# MMC_DSP_interface.net
KiCad netlist of a schematic drawn in EAGLE
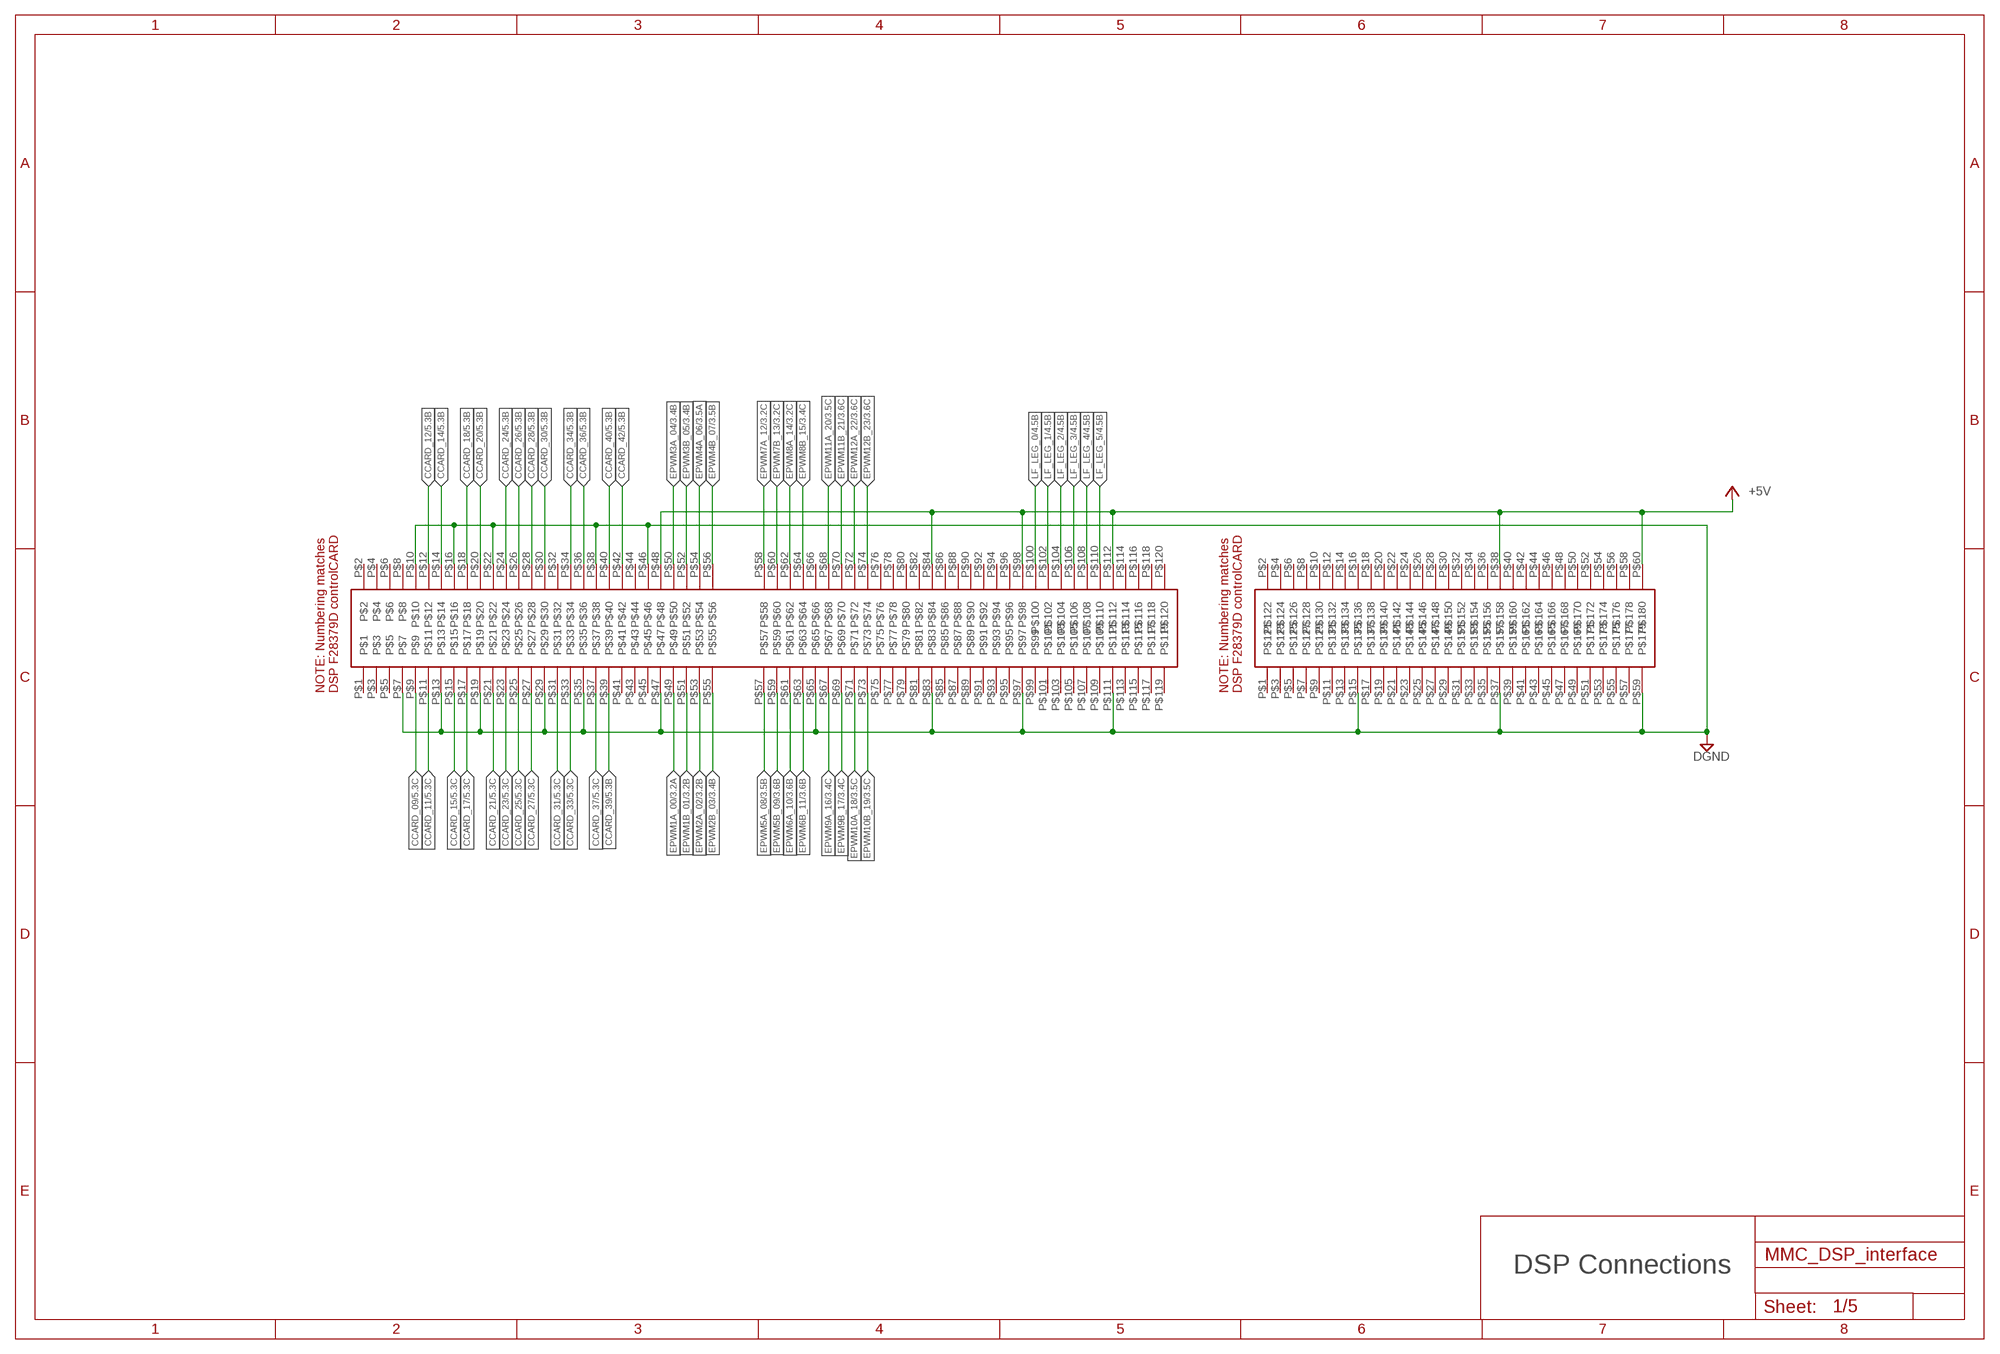
[diagram p0: schematic, sheet 1]
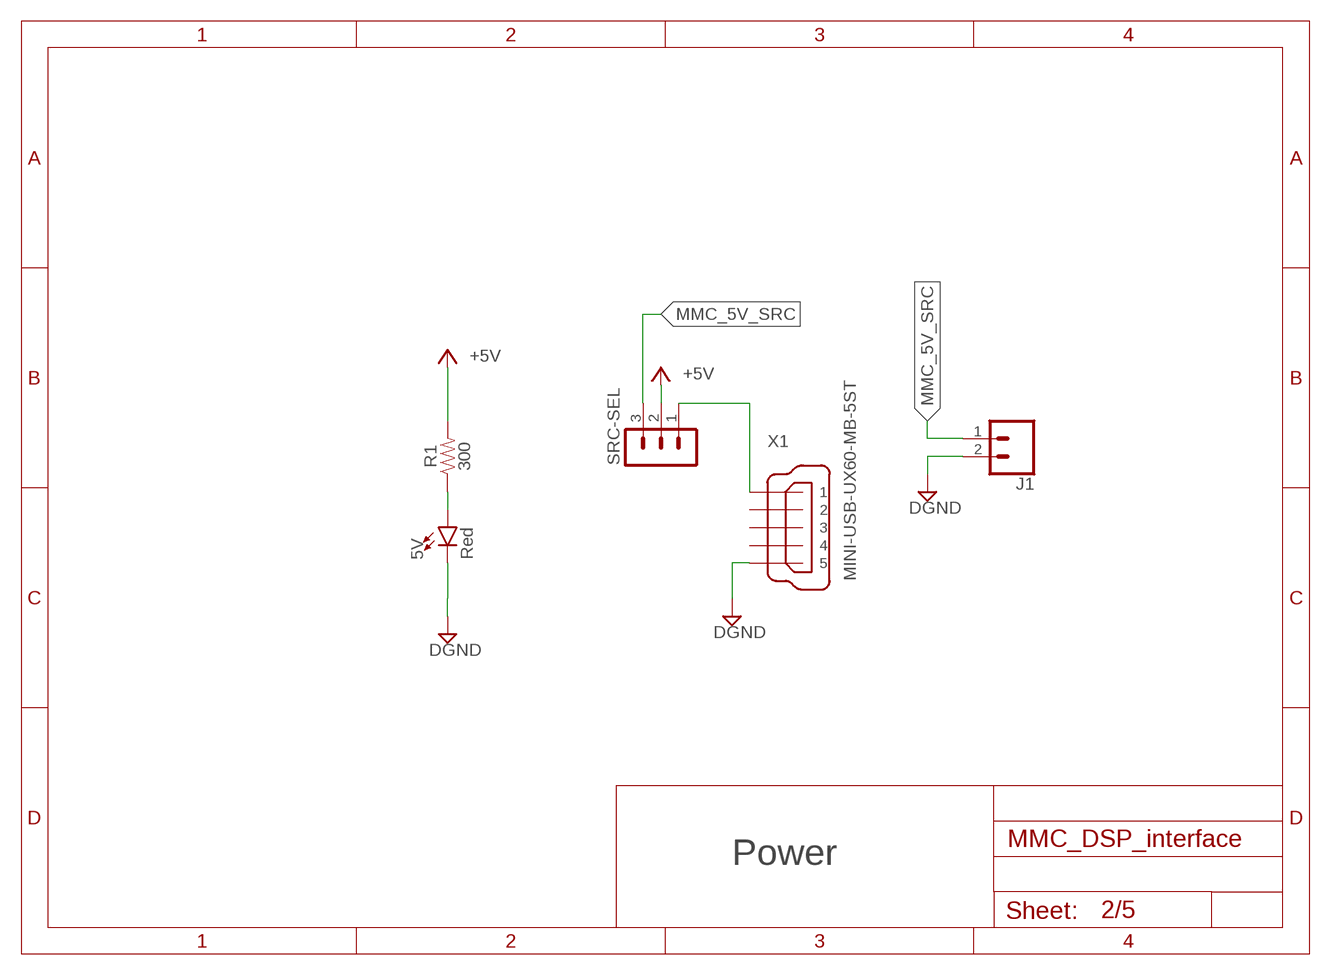
[diagram p1: schematic, sheet 2]
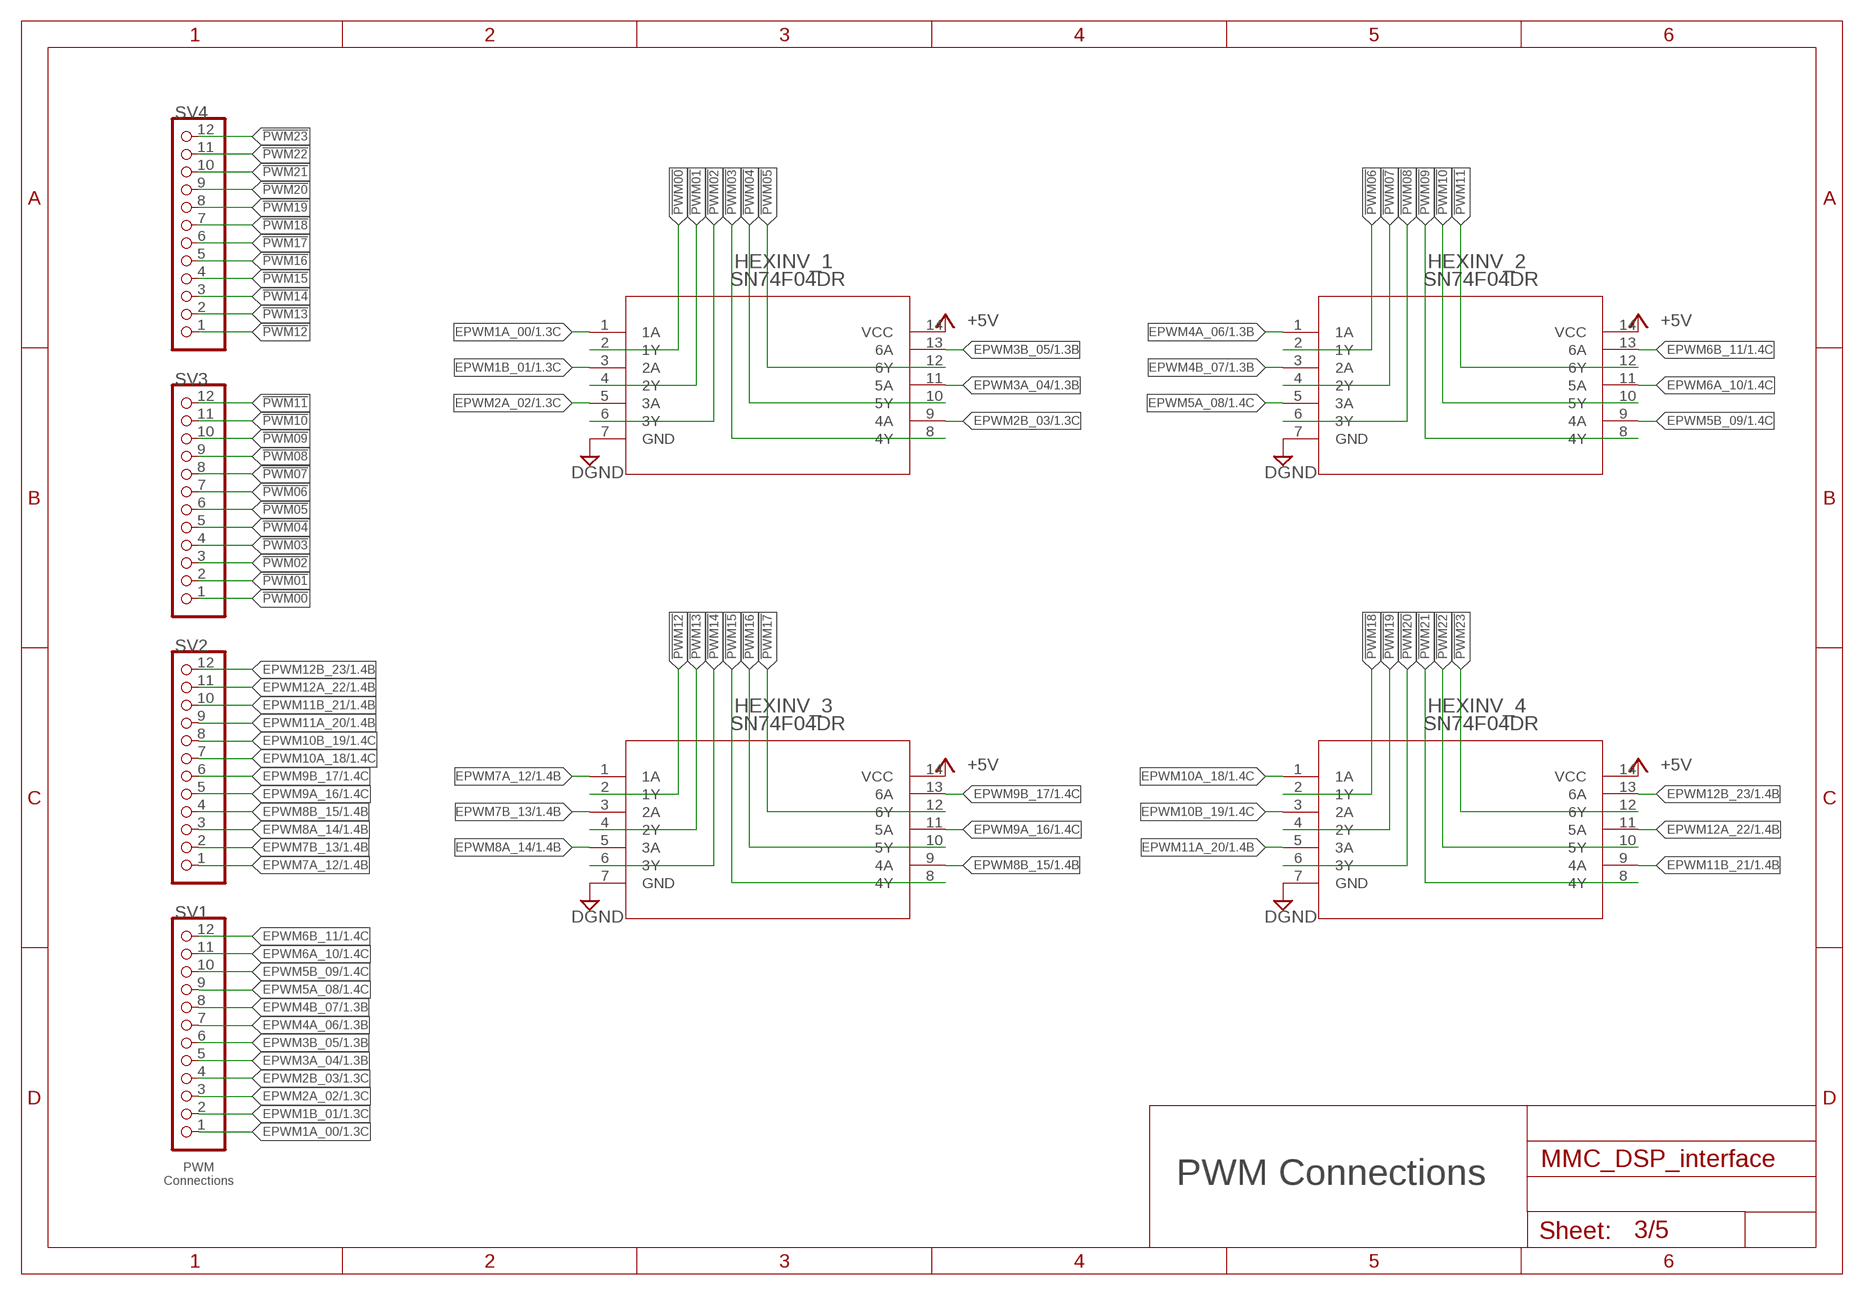
[diagram p2: schematic, sheet 3]
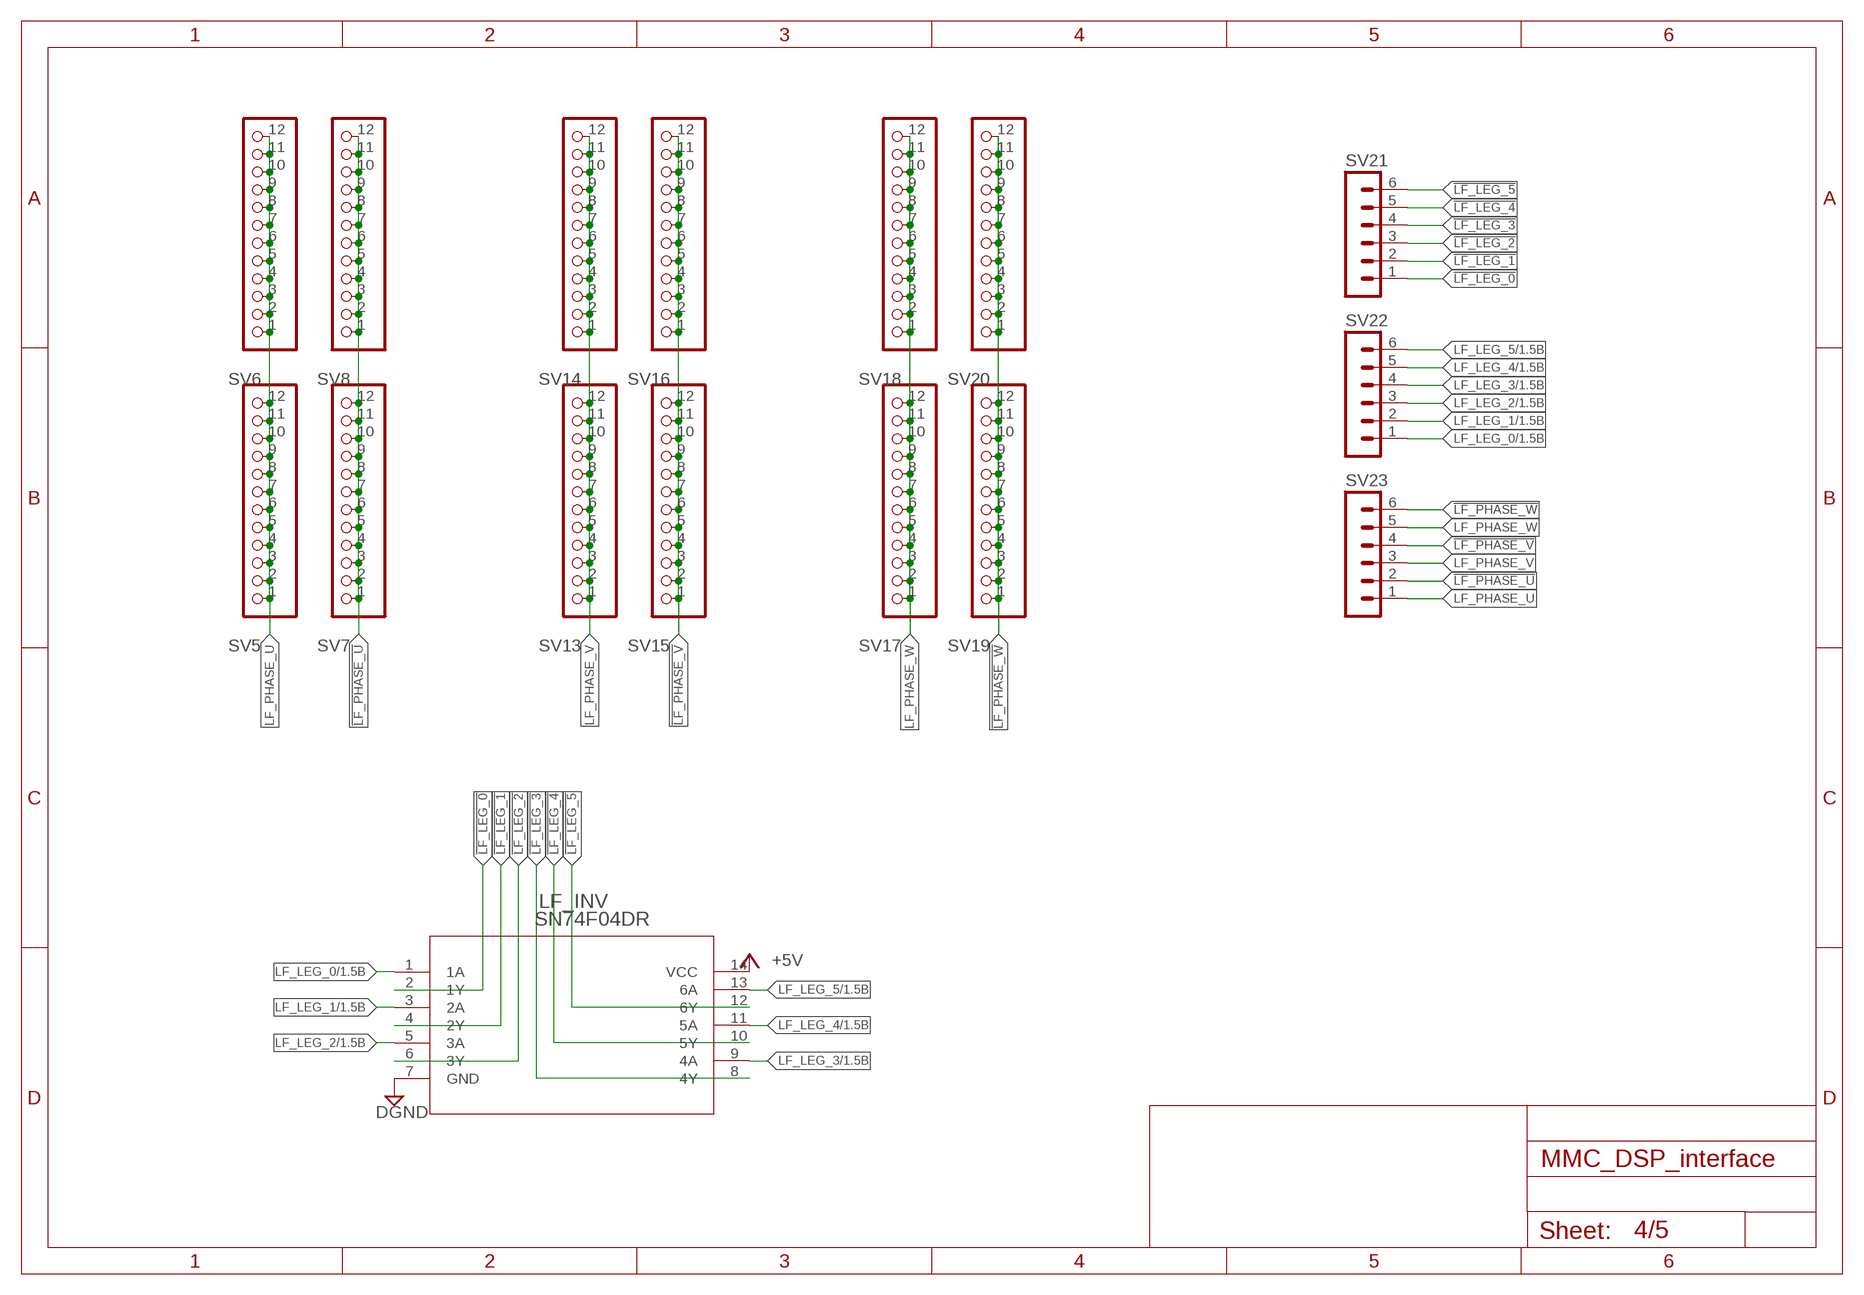
[diagram p3: schematic, sheet 4]
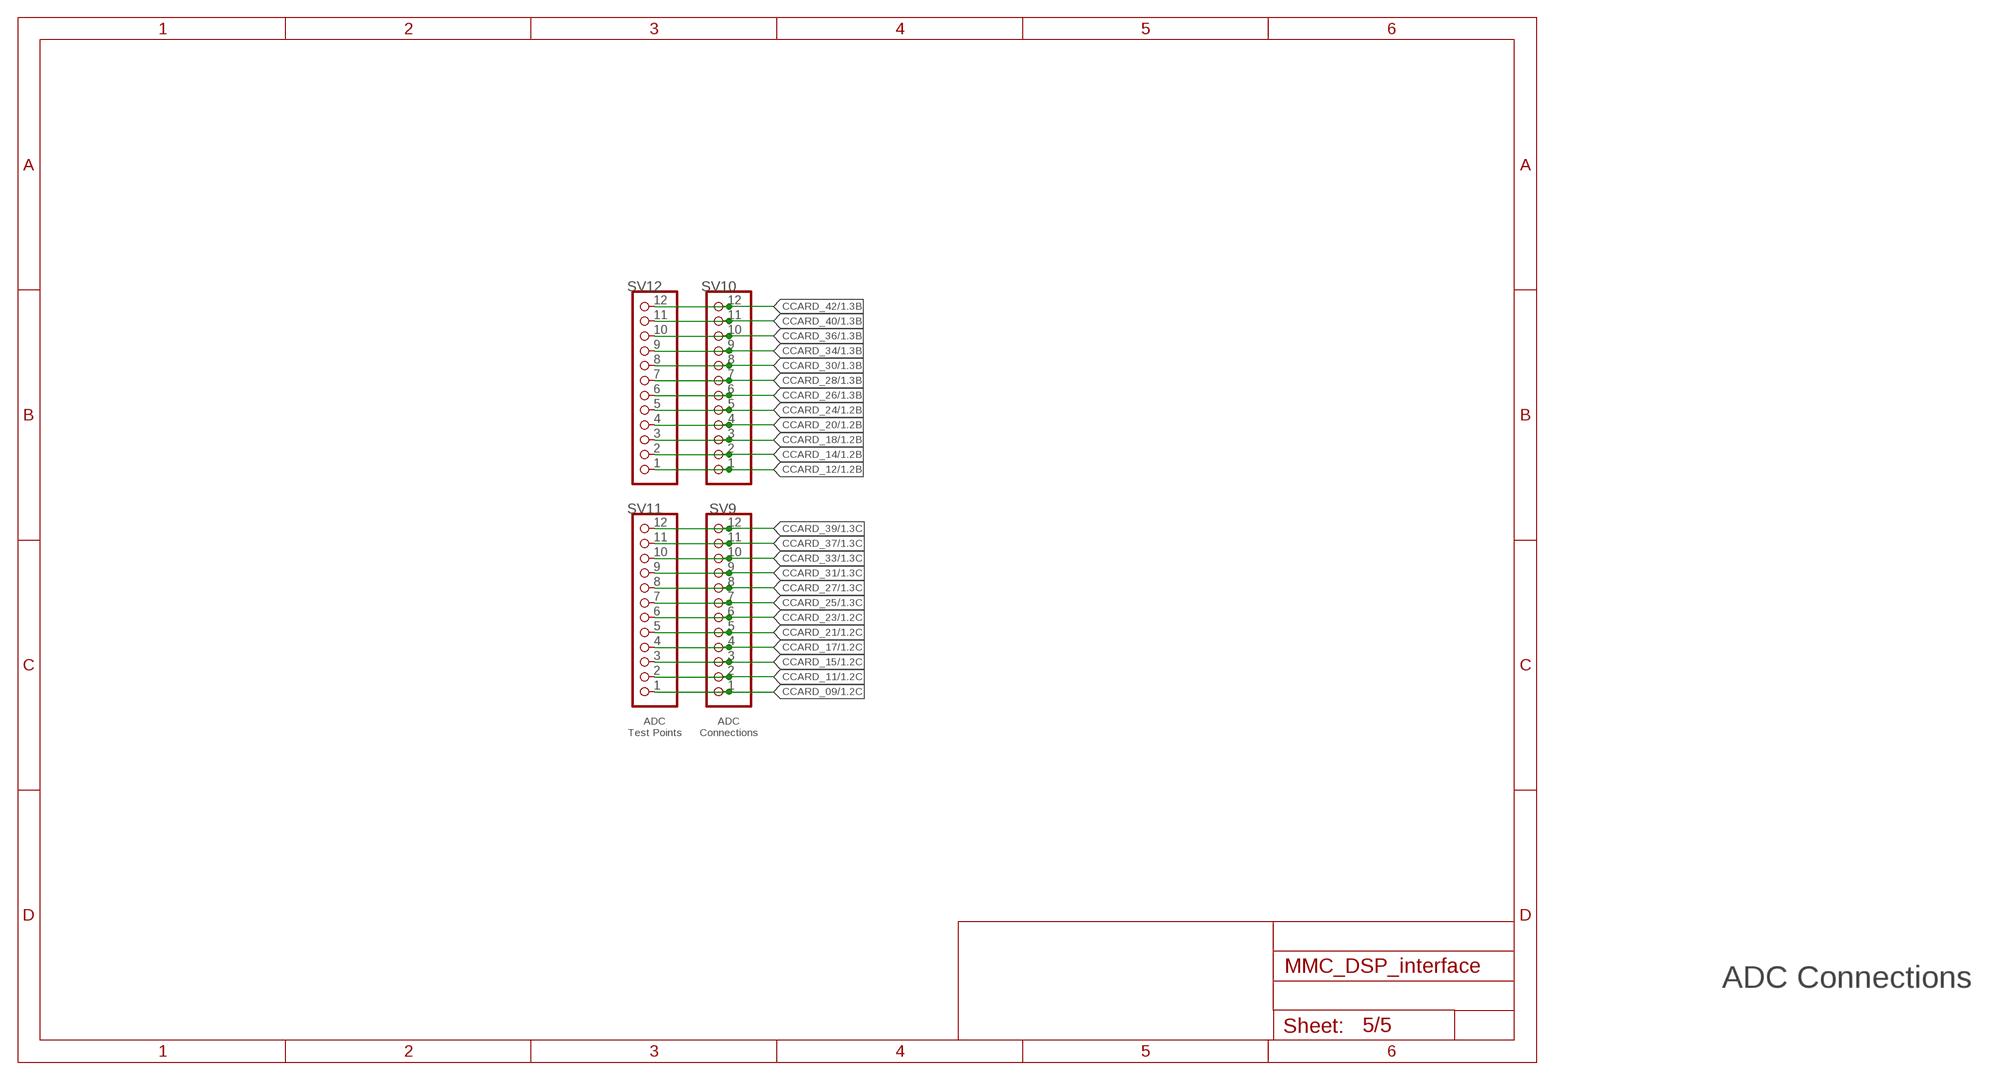
[diagram p4: schematic, sheet 5]

(export (version "E")
  (design (tool "Eeschema 10.0.6"))
  (components
    (comp (ref "5V")
      (value "Red")
      (footprint "eagle-import:LED-0603")
      (libsource (lib "eagle-import") (part "LED-RED0603-SMART"))
    )
    (comp (ref "J1")
      (value "CONN_02")
      (footprint "eagle-import:1X02")
      (libsource (lib "eagle-import") (part "CONN_02"))
    )
    (comp (ref "R1")
      (value "300")
      (footprint "eagle-import:0603")
      (libsource (lib "eagle-import") (part "300OHM-0603-1/10W-1%"))
    )
    (comp (ref "SRC-SEL")
      (value "MA03-1")
      (footprint "eagle-import:MA03-1")
      (libsource (lib "eagle-import") (part "MA03-1"))
    )
    (comp (ref "X1")
      (value "MINI-USB-UX60-MB-5ST")
      (footprint "eagle-import:UX60-MB-5ST")
      (libsource (lib "eagle-import") (part "MINI-USB-UX60-MB-5ST"))
    )
    (comp (ref "LF_INV")
      (value "SN74F04DR")
      (footprint "eagle-import:D14")
      (libsource (lib "eagle-import") (part "SN74F04DR"))
    )
    (comp (ref "SV5")
      (value "PINHD-1X12-CB")
      (footprint "eagle-import:1X12-CB")
      (libsource (lib "eagle-import") (part "PINHD-1X12-CB"))
    )
    (comp (ref "SV6")
      (value "PINHD-1X12-CB")
      (footprint "eagle-import:1X12-CB")
      (libsource (lib "eagle-import") (part "PINHD-1X12-CB"))
    )
    (comp (ref "SV7")
      (value "PINHD-1X12-CB")
      (footprint "eagle-import:1X12-CB")
      (libsource (lib "eagle-import") (part "PINHD-1X12-CB"))
    )
    (comp (ref "SV8")
      (value "PINHD-1X12-CB")
      (footprint "eagle-import:1X12-CB")
      (libsource (lib "eagle-import") (part "PINHD-1X12-CB"))
    )
    (comp (ref "SV13")
      (value "PINHD-1X12-CB")
      (footprint "eagle-import:1X12-CB")
      (libsource (lib "eagle-import") (part "PINHD-1X12-CB"))
    )
    (comp (ref "SV14")
      (value "PINHD-1X12-CB")
      (footprint "eagle-import:1X12-CB")
      (libsource (lib "eagle-import") (part "PINHD-1X12-CB"))
    )
    (comp (ref "SV15")
      (value "PINHD-1X12-CB")
      (footprint "eagle-import:1X12-CB")
      (libsource (lib "eagle-import") (part "PINHD-1X12-CB"))
    )
    (comp (ref "SV16")
      (value "PINHD-1X12-CB")
      (footprint "eagle-import:1X12-CB")
      (libsource (lib "eagle-import") (part "PINHD-1X12-CB"))
    )
    (comp (ref "SV17")
      (value "PINHD-1X12-CB")
      (footprint "eagle-import:1X12-CB")
      (libsource (lib "eagle-import") (part "PINHD-1X12-CB"))
    )
    (comp (ref "SV18")
      (value "PINHD-1X12-CB")
      (footprint "eagle-import:1X12-CB")
      (libsource (lib "eagle-import") (part "PINHD-1X12-CB"))
    )
    (comp (ref "SV19")
      (value "PINHD-1X12-CB")
      (footprint "eagle-import:1X12-CB")
      (libsource (lib "eagle-import") (part "PINHD-1X12-CB"))
    )
    (comp (ref "SV20")
      (value "PINHD-1X12-CB")
      (footprint "eagle-import:1X12-CB")
      (libsource (lib "eagle-import") (part "PINHD-1X12-CB"))
    )
    (comp (ref "SV21")
      (value "MA06-1")
      (footprint "eagle-import:MA06-1")
      (libsource (lib "eagle-import") (part "MA06-1"))
    )
    (comp (ref "SV22")
      (value "MA06-1")
      (footprint "eagle-import:MA06-1")
      (libsource (lib "eagle-import") (part "MA06-1"))
    )
    (comp (ref "SV23")
      (value "MA06-1")
      (footprint "eagle-import:MA06-1")
      (libsource (lib "eagle-import") (part "MA06-1"))
    )
    (comp (ref "HEXINV_1")
      (value "SN74F04DR")
      (footprint "eagle-import:D14")
      (libsource (lib "eagle-import") (part "SN74F04DR"))
    )
    (comp (ref "HEXINV_2")
      (value "SN74F04DR")
      (footprint "eagle-import:D14")
      (libsource (lib "eagle-import") (part "SN74F04DR"))
    )
    (comp (ref "HEXINV_3")
      (value "SN74F04DR")
      (footprint "eagle-import:D14")
      (libsource (lib "eagle-import") (part "SN74F04DR"))
    )
    (comp (ref "HEXINV_4")
      (value "SN74F04DR")
      (footprint "eagle-import:D14")
      (libsource (lib "eagle-import") (part "SN74F04DR"))
    )
    (comp (ref "SV1")
      (value "PINHD-1X12-CB")
      (footprint "eagle-import:1X12-CB")
      (libsource (lib "eagle-import") (part "PINHD-1X12-CB"))
    )
    (comp (ref "SV2")
      (value "PINHD-1X12-CB")
      (footprint "eagle-import:1X12-CB")
      (libsource (lib "eagle-import") (part "PINHD-1X12-CB"))
    )
    (comp (ref "SV3")
      (value "PINHD-1X12-CB")
      (footprint "eagle-import:1X12-CB")
      (libsource (lib "eagle-import") (part "PINHD-1X12-CB"))
    )
    (comp (ref "SV4")
      (value "PINHD-1X12-CB")
      (footprint "eagle-import:1X12-CB")
      (libsource (lib "eagle-import") (part "PINHD-1X12-CB"))
    )
    (comp (ref "U$1")
      (value "HSEC8-160-01-L-DV-A-BL")
      (footprint "eagle-import:HSEC8-160-01-L-DV-A-BL")
      (libsource (lib "eagle-import") (part "HSEC8-160-01-L-DV-A-BL"))
    )
    (comp (ref "U$2")
      (value "HSEC8-130-01-SM-DV-A")
      (footprint "eagle-import:HSEC8-130-01-SM-DV-A")
      (libsource (lib "eagle-import") (part "HSEC8-130-01-SM-DV-A"))
    )
    (comp (ref "SV9")
      (value "PINHD-1X12-CB")
      (footprint "eagle-import:1X12-CB")
      (libsource (lib "eagle-import") (part "PINHD-1X12-CB"))
    )
    (comp (ref "SV10")
      (value "PINHD-1X12-CB")
      (footprint "eagle-import:1X12-CB")
      (libsource (lib "eagle-import") (part "PINHD-1X12-CB"))
    )
    (comp (ref "SV11")
      (value "PINHD-1X12-CB")
      (footprint "eagle-import:1X12-CB")
      (libsource (lib "eagle-import") (part "PINHD-1X12-CB"))
    )
    (comp (ref "SV12")
      (value "PINHD-1X12-CB")
      (footprint "eagle-import:1X12-CB")
      (libsource (lib "eagle-import") (part "PINHD-1X12-CB"))
    )
  )
  (nets
    (net (code "1") (name "+5V") (class "Default")
      (node (ref "HEXINV_1") (pin "14") (pinfunction "VCC_14") (pintype "power_in"))
      (node (ref "HEXINV_2") (pin "14") (pinfunction "VCC_14") (pintype "power_in"))
      (node (ref "HEXINV_3") (pin "14") (pinfunction "VCC_14") (pintype "power_in"))
      (node (ref "HEXINV_4") (pin "14") (pinfunction "VCC_14") (pintype "power_in"))
      (node (ref "LF_INV") (pin "14") (pinfunction "VCC_14") (pintype "power_in"))
      (node (ref "R1") (pin "2") (pinfunction "2_2") (pintype "passive"))
      (node (ref "SRC-SEL") (pin "2") (pinfunction "2_2") (pintype "passive"))
      (node (ref "U$1") (pin "P$112") (pinfunction "P$112_P$112") (pintype "bidirectional"))
      (node (ref "U$1") (pin "P$48") (pinfunction "P$48_P$48") (pintype "bidirectional"))
      (node (ref "U$1") (pin "P$84") (pinfunction "P$84_P$84") (pintype "bidirectional"))
      (node (ref "U$1") (pin "P$98") (pinfunction "P$98_P$98") (pintype "bidirectional"))
      (node (ref "U$2") (pin "P$38") (pinfunction "P$158_P$38") (pintype "bidirectional"))
      (node (ref "U$2") (pin "P$60") (pinfunction "P$180_P$60") (pintype "bidirectional"))
    )
    (net (code "2") (name "CCARD_09") (class "Default")
      (node (ref "SV11") (pin "1") (pinfunction "1_1") (pintype "passive"))
      (node (ref "SV9") (pin "1") (pinfunction "1_1") (pintype "passive"))
      (node (ref "U$1") (pin "P$9") (pinfunction "P$9_P$9") (pintype "bidirectional"))
    )
    (net (code "3") (name "CCARD_11") (class "Default")
      (node (ref "SV11") (pin "2") (pinfunction "2_2") (pintype "passive"))
      (node (ref "SV9") (pin "2") (pinfunction "2_2") (pintype "passive"))
      (node (ref "U$1") (pin "P$11") (pinfunction "P$11_P$11") (pintype "bidirectional"))
    )
    (net (code "4") (name "CCARD_12") (class "Default")
      (node (ref "SV10") (pin "1") (pinfunction "1_1") (pintype "passive"))
      (node (ref "SV12") (pin "1") (pinfunction "1_1") (pintype "passive"))
      (node (ref "U$1") (pin "P$12") (pinfunction "P$12_P$12") (pintype "bidirectional"))
    )
    (net (code "5") (name "CCARD_14") (class "Default")
      (node (ref "SV10") (pin "2") (pinfunction "2_2") (pintype "passive"))
      (node (ref "SV12") (pin "2") (pinfunction "2_2") (pintype "passive"))
      (node (ref "U$1") (pin "P$14") (pinfunction "P$14_P$14") (pintype "bidirectional"))
    )
    (net (code "6") (name "CCARD_15") (class "Default")
      (node (ref "SV11") (pin "3") (pinfunction "3_3") (pintype "passive"))
      (node (ref "SV9") (pin "3") (pinfunction "3_3") (pintype "passive"))
      (node (ref "U$1") (pin "P$15") (pinfunction "P$15_P$15") (pintype "bidirectional"))
    )
    (net (code "7") (name "CCARD_17") (class "Default")
      (node (ref "SV11") (pin "4") (pinfunction "4_4") (pintype "passive"))
      (node (ref "SV9") (pin "4") (pinfunction "4_4") (pintype "passive"))
      (node (ref "U$1") (pin "P$17") (pinfunction "P$17_P$17") (pintype "bidirectional"))
    )
    (net (code "8") (name "CCARD_18") (class "Default")
      (node (ref "SV10") (pin "3") (pinfunction "3_3") (pintype "passive"))
      (node (ref "SV12") (pin "3") (pinfunction "3_3") (pintype "passive"))
      (node (ref "U$1") (pin "P$18") (pinfunction "P$18_P$18") (pintype "bidirectional"))
    )
    (net (code "9") (name "CCARD_20") (class "Default")
      (node (ref "SV10") (pin "4") (pinfunction "4_4") (pintype "passive"))
      (node (ref "SV12") (pin "4") (pinfunction "4_4") (pintype "passive"))
      (node (ref "U$1") (pin "P$20") (pinfunction "P$20_P$20") (pintype "bidirectional"))
    )
    (net (code "10") (name "CCARD_21") (class "Default")
      (node (ref "SV11") (pin "5") (pinfunction "5_5") (pintype "passive"))
      (node (ref "SV9") (pin "5") (pinfunction "5_5") (pintype "passive"))
      (node (ref "U$1") (pin "P$21") (pinfunction "P$21_P$21") (pintype "bidirectional"))
    )
    (net (code "11") (name "CCARD_23") (class "Default")
      (node (ref "SV11") (pin "6") (pinfunction "6_6") (pintype "passive"))
      (node (ref "SV9") (pin "6") (pinfunction "6_6") (pintype "passive"))
      (node (ref "U$1") (pin "P$23") (pinfunction "P$23_P$23") (pintype "bidirectional"))
    )
    (net (code "12") (name "CCARD_24") (class "Default")
      (node (ref "SV10") (pin "5") (pinfunction "5_5") (pintype "passive"))
      (node (ref "SV12") (pin "5") (pinfunction "5_5") (pintype "passive"))
      (node (ref "U$1") (pin "P$24") (pinfunction "P$24_P$24") (pintype "bidirectional"))
    )
    (net (code "13") (name "CCARD_25") (class "Default")
      (node (ref "SV11") (pin "7") (pinfunction "7_7") (pintype "passive"))
      (node (ref "SV9") (pin "7") (pinfunction "7_7") (pintype "passive"))
      (node (ref "U$1") (pin "P$25") (pinfunction "P$25_P$25") (pintype "bidirectional"))
    )
    (net (code "14") (name "CCARD_26") (class "Default")
      (node (ref "SV10") (pin "6") (pinfunction "6_6") (pintype "passive"))
      (node (ref "SV12") (pin "6") (pinfunction "6_6") (pintype "passive"))
      (node (ref "U$1") (pin "P$26") (pinfunction "P$26_P$26") (pintype "bidirectional"))
    )
    (net (code "15") (name "CCARD_27") (class "Default")
      (node (ref "SV11") (pin "8") (pinfunction "8_8") (pintype "passive"))
      (node (ref "SV9") (pin "8") (pinfunction "8_8") (pintype "passive"))
      (node (ref "U$1") (pin "P$27") (pinfunction "P$27_P$27") (pintype "bidirectional"))
    )
    (net (code "16") (name "CCARD_28") (class "Default")
      (node (ref "SV10") (pin "7") (pinfunction "7_7") (pintype "passive"))
      (node (ref "SV12") (pin "7") (pinfunction "7_7") (pintype "passive"))
      (node (ref "U$1") (pin "P$28") (pinfunction "P$28_P$28") (pintype "bidirectional"))
    )
    (net (code "17") (name "CCARD_30") (class "Default")
      (node (ref "SV10") (pin "8") (pinfunction "8_8") (pintype "passive"))
      (node (ref "SV12") (pin "8") (pinfunction "8_8") (pintype "passive"))
      (node (ref "U$1") (pin "P$30") (pinfunction "P$30_P$30") (pintype "bidirectional"))
    )
    (net (code "18") (name "CCARD_31") (class "Default")
      (node (ref "SV11") (pin "9") (pinfunction "9_9") (pintype "passive"))
      (node (ref "SV9") (pin "9") (pinfunction "9_9") (pintype "passive"))
      (node (ref "U$1") (pin "P$31") (pinfunction "P$31_P$31") (pintype "bidirectional"))
    )
    (net (code "19") (name "CCARD_33") (class "Default")
      (node (ref "SV11") (pin "10") (pinfunction "10_10") (pintype "passive"))
      (node (ref "SV9") (pin "10") (pinfunction "10_10") (pintype "passive"))
      (node (ref "U$1") (pin "P$33") (pinfunction "P$33_P$33") (pintype "bidirectional"))
    )
    (net (code "20") (name "CCARD_34") (class "Default")
      (node (ref "SV10") (pin "9") (pinfunction "9_9") (pintype "passive"))
      (node (ref "SV12") (pin "9") (pinfunction "9_9") (pintype "passive"))
      (node (ref "U$1") (pin "P$34") (pinfunction "P$34_P$34") (pintype "bidirectional"))
    )
    (net (code "21") (name "CCARD_36") (class "Default")
      (node (ref "SV10") (pin "10") (pinfunction "10_10") (pintype "passive"))
      (node (ref "SV12") (pin "10") (pinfunction "10_10") (pintype "passive"))
      (node (ref "U$1") (pin "P$36") (pinfunction "P$36_P$36") (pintype "bidirectional"))
    )
    (net (code "22") (name "CCARD_37") (class "Default")
      (node (ref "SV11") (pin "11") (pinfunction "11_11") (pintype "passive"))
      (node (ref "SV9") (pin "11") (pinfunction "11_11") (pintype "passive"))
      (node (ref "U$1") (pin "P$37") (pinfunction "P$37_P$37") (pintype "bidirectional"))
    )
    (net (code "23") (name "CCARD_39") (class "Default")
      (node (ref "SV11") (pin "12") (pinfunction "12_12") (pintype "passive"))
      (node (ref "SV9") (pin "12") (pinfunction "12_12") (pintype "passive"))
      (node (ref "U$1") (pin "P$39") (pinfunction "P$39_P$39") (pintype "bidirectional"))
    )
    (net (code "24") (name "CCARD_40") (class "Default")
      (node (ref "SV10") (pin "11") (pinfunction "11_11") (pintype "passive"))
      (node (ref "SV12") (pin "11") (pinfunction "11_11") (pintype "passive"))
      (node (ref "U$1") (pin "P$40") (pinfunction "P$40_P$40") (pintype "bidirectional"))
    )
    (net (code "25") (name "CCARD_42") (class "Default")
      (node (ref "SV10") (pin "12") (pinfunction "12_12") (pintype "passive"))
      (node (ref "SV12") (pin "12") (pinfunction "12_12") (pintype "passive"))
      (node (ref "U$1") (pin "P$42") (pinfunction "P$42_P$42") (pintype "bidirectional"))
    )
    (net (code "26") (name "DGND") (class "Default")
      (node (ref "5V") (pin "C") (pinfunction "C_C") (pintype "passive"))
      (node (ref "HEXINV_1") (pin "7") (pinfunction "GND_7") (pintype "power_in"))
      (node (ref "HEXINV_2") (pin "7") (pinfunction "GND_7") (pintype "power_in"))
      (node (ref "HEXINV_3") (pin "7") (pinfunction "GND_7") (pintype "power_in"))
      (node (ref "HEXINV_4") (pin "7") (pinfunction "GND_7") (pintype "power_in"))
      (node (ref "J1") (pin "2") (pinfunction "2_2") (pintype "passive"))
      (node (ref "LF_INV") (pin "7") (pinfunction "GND_7") (pintype "power_in"))
      (node (ref "U$1") (pin "P$10") (pinfunction "P$10_P$10") (pintype "bidirectional"))
      (node (ref "U$1") (pin "P$111") (pinfunction "P$111_P$111") (pintype "bidirectional"))
      (node (ref "U$1") (pin "P$13") (pinfunction "P$13_P$13") (pintype "bidirectional"))
      (node (ref "U$1") (pin "P$16") (pinfunction "P$16_P$16") (pintype "bidirectional"))
      (node (ref "U$1") (pin "P$19") (pinfunction "P$19_P$19") (pintype "bidirectional"))
      (node (ref "U$1") (pin "P$22") (pinfunction "P$22_P$22") (pintype "bidirectional"))
      (node (ref "U$1") (pin "P$29") (pinfunction "P$29_P$29") (pintype "bidirectional"))
      (node (ref "U$1") (pin "P$35") (pinfunction "P$35_P$35") (pintype "bidirectional"))
      (node (ref "U$1") (pin "P$38") (pinfunction "P$38_P$38") (pintype "bidirectional"))
      (node (ref "U$1") (pin "P$46") (pinfunction "P$46_P$46") (pintype "bidirectional"))
      (node (ref "U$1") (pin "P$47") (pinfunction "P$47_P$47") (pintype "bidirectional"))
      (node (ref "U$1") (pin "P$65") (pinfunction "P$65_P$65") (pintype "bidirectional"))
      (node (ref "U$1") (pin "P$7") (pinfunction "P$7_P$7") (pintype "bidirectional"))
      (node (ref "U$1") (pin "P$83") (pinfunction "P$83_P$83") (pintype "bidirectional"))
      (node (ref "U$1") (pin "P$97") (pinfunction "P$97_P$97") (pintype "bidirectional"))
      (node (ref "U$2") (pin "P$15") (pinfunction "P$135_P$15") (pintype "bidirectional"))
      (node (ref "U$2") (pin "P$37") (pinfunction "P$157_P$37") (pintype "bidirectional"))
      (node (ref "U$2") (pin "P$59") (pinfunction "P$179_P$59") (pintype "bidirectional"))
      (node (ref "X1") (pin "5") (pinfunction "5_5") (pintype "input"))
    )
    (net (code "27") (name "EPWM1A_00") (class "Default")
      (node (ref "HEXINV_1") (pin "1") (pinfunction "1A_1") (pintype "input"))
      (node (ref "SV1") (pin "1") (pinfunction "1_1") (pintype "passive"))
      (node (ref "U$1") (pin "P$49") (pinfunction "P$49_P$49") (pintype "bidirectional"))
    )
    (net (code "28") (name "EPWM1B_01") (class "Default")
      (node (ref "HEXINV_1") (pin "3") (pinfunction "2A_3") (pintype "input"))
      (node (ref "SV1") (pin "2") (pinfunction "2_2") (pintype "passive"))
      (node (ref "U$1") (pin "P$51") (pinfunction "P$51_P$51") (pintype "bidirectional"))
    )
    (net (code "29") (name "EPWM2A_02") (class "Default")
      (node (ref "HEXINV_1") (pin "5") (pinfunction "3A_5") (pintype "input"))
      (node (ref "SV1") (pin "3") (pinfunction "3_3") (pintype "passive"))
      (node (ref "U$1") (pin "P$53") (pinfunction "P$53_P$53") (pintype "bidirectional"))
    )
    (net (code "30") (name "EPWM2B_03") (class "Default")
      (node (ref "HEXINV_1") (pin "9") (pinfunction "4A_9") (pintype "input"))
      (node (ref "SV1") (pin "4") (pinfunction "4_4") (pintype "passive"))
      (node (ref "U$1") (pin "P$55") (pinfunction "P$55_P$55") (pintype "bidirectional"))
    )
    (net (code "31") (name "EPWM3A_04") (class "Default")
      (node (ref "HEXINV_1") (pin "11") (pinfunction "5A_11") (pintype "input"))
      (node (ref "SV1") (pin "5") (pinfunction "5_5") (pintype "passive"))
      (node (ref "U$1") (pin "P$50") (pinfunction "P$50_P$50") (pintype "bidirectional"))
    )
    (net (code "32") (name "EPWM3B_05") (class "Default")
      (node (ref "HEXINV_1") (pin "13") (pinfunction "6A_13") (pintype "input"))
      (node (ref "SV1") (pin "6") (pinfunction "6_6") (pintype "passive"))
      (node (ref "U$1") (pin "P$52") (pinfunction "P$52_P$52") (pintype "bidirectional"))
    )
    (net (code "33") (name "EPWM4A_06") (class "Default")
      (node (ref "HEXINV_2") (pin "1") (pinfunction "1A_1") (pintype "input"))
      (node (ref "SV1") (pin "7") (pinfunction "7_7") (pintype "passive"))
      (node (ref "U$1") (pin "P$54") (pinfunction "P$54_P$54") (pintype "bidirectional"))
    )
    (net (code "34") (name "EPWM4B_07") (class "Default")
      (node (ref "HEXINV_2") (pin "3") (pinfunction "2A_3") (pintype "input"))
      (node (ref "SV1") (pin "8") (pinfunction "8_8") (pintype "passive"))
      (node (ref "U$1") (pin "P$56") (pinfunction "P$56_P$56") (pintype "bidirectional"))
    )
    (net (code "35") (name "EPWM5A_08") (class "Default")
      (node (ref "HEXINV_2") (pin "5") (pinfunction "3A_5") (pintype "input"))
      (node (ref "SV1") (pin "9") (pinfunction "9_9") (pintype "passive"))
      (node (ref "U$1") (pin "P$57") (pinfunction "P$57_P$57") (pintype "bidirectional"))
    )
    (net (code "36") (name "EPWM5B_09") (class "Default")
      (node (ref "HEXINV_2") (pin "9") (pinfunction "4A_9") (pintype "input"))
      (node (ref "SV1") (pin "10") (pinfunction "10_10") (pintype "passive"))
      (node (ref "U$1") (pin "P$59") (pinfunction "P$59_P$59") (pintype "bidirectional"))
    )
    (net (code "37") (name "EPWM6A_10") (class "Default")
      (node (ref "HEXINV_2") (pin "11") (pinfunction "5A_11") (pintype "input"))
      (node (ref "SV1") (pin "11") (pinfunction "11_11") (pintype "passive"))
      (node (ref "U$1") (pin "P$61") (pinfunction "P$61_P$61") (pintype "bidirectional"))
    )
    (net (code "38") (name "EPWM6B_11") (class "Default")
      (node (ref "HEXINV_2") (pin "13") (pinfunction "6A_13") (pintype "input"))
      (node (ref "SV1") (pin "12") (pinfunction "12_12") (pintype "passive"))
      (node (ref "U$1") (pin "P$63") (pinfunction "P$63_P$63") (pintype "bidirectional"))
    )
    (net (code "39") (name "EPWM7A_12") (class "Default")
      (node (ref "HEXINV_3") (pin "1") (pinfunction "1A_1") (pintype "input"))
      (node (ref "SV2") (pin "1") (pinfunction "1_1") (pintype "passive"))
      (node (ref "U$1") (pin "P$58") (pinfunction "P$58_P$58") (pintype "bidirectional"))
    )
    (net (code "40") (name "EPWM7B_13") (class "Default")
      (node (ref "HEXINV_3") (pin "3") (pinfunction "2A_3") (pintype "input"))
      (node (ref "SV2") (pin "2") (pinfunction "2_2") (pintype "passive"))
      (node (ref "U$1") (pin "P$60") (pinfunction "P$60_P$60") (pintype "bidirectional"))
    )
    (net (code "41") (name "EPWM8A_14") (class "Default")
      (node (ref "HEXINV_3") (pin "5") (pinfunction "3A_5") (pintype "input"))
      (node (ref "SV2") (pin "3") (pinfunction "3_3") (pintype "passive"))
      (node (ref "U$1") (pin "P$62") (pinfunction "P$62_P$62") (pintype "bidirectional"))
    )
    (net (code "42") (name "EPWM8B_15") (class "Default")
      (node (ref "HEXINV_3") (pin "9") (pinfunction "4A_9") (pintype "input"))
      (node (ref "SV2") (pin "4") (pinfunction "4_4") (pintype "passive"))
      (node (ref "U$1") (pin "P$64") (pinfunction "P$64_P$64") (pintype "bidirectional"))
    )
    (net (code "43") (name "EPWM9A_16") (class "Default")
      (node (ref "HEXINV_3") (pin "11") (pinfunction "5A_11") (pintype "input"))
      (node (ref "SV2") (pin "5") (pinfunction "5_5") (pintype "passive"))
      (node (ref "U$1") (pin "P$67") (pinfunction "P$67_P$67") (pintype "bidirectional"))
    )
    (net (code "44") (name "EPWM9B_17") (class "Default")
      (node (ref "HEXINV_3") (pin "13") (pinfunction "6A_13") (pintype "input"))
      (node (ref "SV2") (pin "6") (pinfunction "6_6") (pintype "passive"))
      (node (ref "U$1") (pin "P$69") (pinfunction "P$69_P$69") (pintype "bidirectional"))
    )
    (net (code "45") (name "EPWM10A_18") (class "Default")
      (node (ref "HEXINV_4") (pin "1") (pinfunction "1A_1") (pintype "input"))
      (node (ref "SV2") (pin "7") (pinfunction "7_7") (pintype "passive"))
      (node (ref "U$1") (pin "P$71") (pinfunction "P$71_P$71") (pintype "bidirectional"))
    )
    (net (code "46") (name "EPWM10B_19") (class "Default")
      (node (ref "HEXINV_4") (pin "3") (pinfunction "2A_3") (pintype "input"))
      (node (ref "SV2") (pin "8") (pinfunction "8_8") (pintype "passive"))
      (node (ref "U$1") (pin "P$73") (pinfunction "P$73_P$73") (pintype "bidirectional"))
    )
    (net (code "47") (name "EPWM11A_20") (class "Default")
      (node (ref "HEXINV_4") (pin "5") (pinfunction "3A_5") (pintype "input"))
      (node (ref "SV2") (pin "9") (pinfunction "9_9") (pintype "passive"))
      (node (ref "U$1") (pin "P$68") (pinfunction "P$68_P$68") (pintype "bidirectional"))
    )
    (net (code "48") (name "EPWM11B_21") (class "Default")
      (node (ref "HEXINV_4") (pin "9") (pinfunction "4A_9") (pintype "input"))
      (node (ref "SV2") (pin "10") (pinfunction "10_10") (pintype "passive"))
      (node (ref "U$1") (pin "P$70") (pinfunction "P$70_P$70") (pintype "bidirectional"))
    )
    (net (code "49") (name "EPWM12A_22") (class "Default")
      (node (ref "HEXINV_4") (pin "11") (pinfunction "5A_11") (pintype "input"))
      (node (ref "SV2") (pin "11") (pinfunction "11_11") (pintype "passive"))
      (node (ref "U$1") (pin "P$72") (pinfunction "P$72_P$72") (pintype "bidirectional"))
    )
    (net (code "50") (name "EPWM12B_23") (class "Default")
      (node (ref "HEXINV_4") (pin "13") (pinfunction "6A_13") (pintype "input"))
      (node (ref "SV2") (pin "12") (pinfunction "12_12") (pintype "passive"))
      (node (ref "U$1") (pin "P$74") (pinfunction "P$74_P$74") (pintype "bidirectional"))
    )
    (net (code "51") (name "LF_LEG_0") (class "Default")
      (node (ref "LF_INV") (pin "1") (pinfunction "1A_1") (pintype "input"))
      (node (ref "SV22") (pin "1") (pinfunction "1_1") (pintype "passive"))
      (node (ref "U$1") (pin "P$100") (pinfunction "P$100_P$100") (pintype "bidirectional"))
    )
    (net (code "52") (name "LF_LEG_1") (class "Default")
      (node (ref "LF_INV") (pin "3") (pinfunction "2A_3") (pintype "input"))
      (node (ref "SV22") (pin "2") (pinfunction "2_2") (pintype "passive"))
      (node (ref "U$1") (pin "P$102") (pinfunction "P$102_P$102") (pintype "bidirectional"))
    )
    (net (code "53") (name "LF_LEG_2") (class "Default")
      (node (ref "LF_INV") (pin "5") (pinfunction "3A_5") (pintype "input"))
      (node (ref "SV22") (pin "3") (pinfunction "3_3") (pintype "passive"))
      (node (ref "U$1") (pin "P$104") (pinfunction "P$104_P$104") (pintype "bidirectional"))
    )
    (net (code "54") (name "LF_LEG_3") (class "Default")
      (node (ref "LF_INV") (pin "9") (pinfunction "4A_9") (pintype "input"))
      (node (ref "SV22") (pin "4") (pinfunction "4_4") (pintype "passive"))
      (node (ref "U$1") (pin "P$106") (pinfunction "P$106_P$106") (pintype "bidirectional"))
    )
    (net (code "55") (name "LF_LEG_4") (class "Default")
      (node (ref "LF_INV") (pin "11") (pinfunction "5A_11") (pintype "input"))
      (node (ref "SV22") (pin "5") (pinfunction "5_5") (pintype "passive"))
      (node (ref "U$1") (pin "P$108") (pinfunction "P$108_P$108") (pintype "bidirectional"))
    )
    (net (code "56") (name "LF_LEG_5") (class "Default")
      (node (ref "LF_INV") (pin "13") (pinfunction "6A_13") (pintype "input"))
      (node (ref "SV22") (pin "6") (pinfunction "6_6") (pintype "passive"))
      (node (ref "U$1") (pin "P$110") (pinfunction "P$110_P$110") (pintype "bidirectional"))
    )
    (net (code "57") (name "LF_PHASE_U") (class "Default")
      (node (ref "SV23") (pin "1") (pinfunction "1_1") (pintype "passive"))
      (node (ref "SV5") (pin "1") (pinfunction "1_1") (pintype "passive"))
      (node (ref "SV5") (pin "10") (pinfunction "10_10") (pintype "passive"))
      (node (ref "SV5") (pin "11") (pinfunction "11_11") (pintype "passive"))
      (node (ref "SV5") (pin "12") (pinfunction "12_12") (pintype "passive"))
      (node (ref "SV5") (pin "2") (pinfunction "2_2") (pintype "passive"))
      (node (ref "SV5") (pin "3") (pinfunction "3_3") (pintype "passive"))
      (node (ref "SV5") (pin "4") (pinfunction "4_4") (pintype "passive"))
      (node (ref "SV5") (pin "5") (pinfunction "5_5") (pintype "passive"))
      (node (ref "SV5") (pin "6") (pinfunction "6_6") (pintype "passive"))
      (node (ref "SV5") (pin "7") (pinfunction "7_7") (pintype "passive"))
      (node (ref "SV5") (pin "8") (pinfunction "8_8") (pintype "passive"))
      (node (ref "SV5") (pin "9") (pinfunction "9_9") (pintype "passive"))
      (node (ref "SV6") (pin "1") (pinfunction "1_1") (pintype "passive"))
      (node (ref "SV6") (pin "10") (pinfunction "10_10") (pintype "passive"))
      (node (ref "SV6") (pin "11") (pinfunction "11_11") (pintype "passive"))
      (node (ref "SV6") (pin "12") (pinfunction "12_12") (pintype "passive"))
      (node (ref "SV6") (pin "2") (pinfunction "2_2") (pintype "passive"))
      (node (ref "SV6") (pin "3") (pinfunction "3_3") (pintype "passive"))
      (node (ref "SV6") (pin "4") (pinfunction "4_4") (pintype "passive"))
      (node (ref "SV6") (pin "5") (pinfunction "5_5") (pintype "passive"))
      (node (ref "SV6") (pin "6") (pinfunction "6_6") (pintype "passive"))
      (node (ref "SV6") (pin "7") (pinfunction "7_7") (pintype "passive"))
      (node (ref "SV6") (pin "8") (pinfunction "8_8") (pintype "passive"))
      (node (ref "SV6") (pin "9") (pinfunction "9_9") (pintype "passive"))
    )
    (net (code "58") (name "LF_PHASE_V") (class "Default")
      (node (ref "SV13") (pin "1") (pinfunction "1_1") (pintype "passive"))
      (node (ref "SV13") (pin "10") (pinfunction "10_10") (pintype "passive"))
      (node (ref "SV13") (pin "11") (pinfunction "11_11") (pintype "passive"))
      (node (ref "SV13") (pin "12") (pinfunction "12_12") (pintype "passive"))
      (node (ref "SV13") (pin "2") (pinfunction "2_2") (pintype "passive"))
      (node (ref "SV13") (pin "3") (pinfunction "3_3") (pintype "passive"))
      (node (ref "SV13") (pin "4") (pinfunction "4_4") (pintype "passive"))
      (node (ref "SV13") (pin "5") (pinfunction "5_5") (pintype "passive"))
      (node (ref "SV13") (pin "6") (pinfunction "6_6") (pintype "passive"))
      (node (ref "SV13") (pin "7") (pinfunction "7_7") (pintype "passive"))
      (node (ref "SV13") (pin "8") (pinfunction "8_8") (pintype "passive"))
      (node (ref "SV13") (pin "9") (pinfunction "9_9") (pintype "passive"))
      (node (ref "SV14") (pin "1") (pinfunction "1_1") (pintype "passive"))
      (node (ref "SV14") (pin "10") (pinfunction "10_10") (pintype "passive"))
      (node (ref "SV14") (pin "11") (pinfunction "11_11") (pintype "passive"))
      (node (ref "SV14") (pin "12") (pinfunction "12_12") (pintype "passive"))
      (node (ref "SV14") (pin "2") (pinfunction "2_2") (pintype "passive"))
      (node (ref "SV14") (pin "3") (pinfunction "3_3") (pintype "passive"))
      (node (ref "SV14") (pin "4") (pinfunction "4_4") (pintype "passive"))
      (node (ref "SV14") (pin "5") (pinfunction "5_5") (pintype "passive"))
      (node (ref "SV14") (pin "6") (pinfunction "6_6") (pintype "passive"))
      (node (ref "SV14") (pin "7") (pinfunction "7_7") (pintype "passive"))
      (node (ref "SV14") (pin "8") (pinfunction "8_8") (pintype "passive"))
      (node (ref "SV14") (pin "9") (pinfunction "9_9") (pintype "passive"))
      (node (ref "SV23") (pin "3") (pinfunction "3_3") (pintype "passive"))
    )
    (net (code "59") (name "LF_PHASE_W") (class "Default")
      (node (ref "SV17") (pin "1") (pinfunction "1_1") (pintype "passive"))
      (node (ref "SV17") (pin "10") (pinfunction "10_10") (pintype "passive"))
      (node (ref "SV17") (pin "11") (pinfunction "11_11") (pintype "passive"))
      (node (ref "SV17") (pin "12") (pinfunction "12_12") (pintype "passive"))
      (node (ref "SV17") (pin "2") (pinfunction "2_2") (pintype "passive"))
      (node (ref "SV17") (pin "3") (pinfunction "3_3") (pintype "passive"))
      (node (ref "SV17") (pin "4") (pinfunction "4_4") (pintype "passive"))
      (node (ref "SV17") (pin "5") (pinfunction "5_5") (pintype "passive"))
      (node (ref "SV17") (pin "6") (pinfunction "6_6") (pintype "passive"))
      (node (ref "SV17") (pin "7") (pinfunction "7_7") (pintype "passive"))
      (node (ref "SV17") (pin "8") (pinfunction "8_8") (pintype "passive"))
      (node (ref "SV17") (pin "9") (pinfunction "9_9") (pintype "passive"))
      (node (ref "SV18") (pin "1") (pinfunction "1_1") (pintype "passive"))
      (node (ref "SV18") (pin "10") (pinfunction "10_10") (pintype "passive"))
      (node (ref "SV18") (pin "11") (pinfunction "11_11") (pintype "passive"))
      (node (ref "SV18") (pin "12") (pinfunction "12_12") (pintype "passive"))
      (node (ref "SV18") (pin "2") (pinfunction "2_2") (pintype "passive"))
      (node (ref "SV18") (pin "3") (pinfunction "3_3") (pintype "passive"))
      (node (ref "SV18") (pin "4") (pinfunction "4_4") (pintype "passive"))
      (node (ref "SV18") (pin "5") (pinfunction "5_5") (pintype "passive"))
      (node (ref "SV18") (pin "6") (pinfunction "6_6") (pintype "passive"))
      (node (ref "SV18") (pin "7") (pinfunction "7_7") (pintype "passive"))
      (node (ref "SV18") (pin "8") (pinfunction "8_8") (pintype "passive"))
      (node (ref "SV18") (pin "9") (pinfunction "9_9") (pintype "passive"))
      (node (ref "SV23") (pin "5") (pinfunction "5_5") (pintype "passive"))
    )
    (net (code "60") (name "MMC_5V_SRC") (class "Default")
      (node (ref "J1") (pin "1") (pinfunction "1_1") (pintype "passive"))
      (node (ref "SRC-SEL") (pin "3") (pinfunction "3_3") (pintype "passive"))
    )
    (net (code "61") (name "Net-(5V-PadA)") (class "Default")
      (node (ref "5V") (pin "A") (pinfunction "A_A") (pintype "passive"))
      (node (ref "R1") (pin "1") (pinfunction "1_1") (pintype "passive"))
    )
    (net (code "62") (name "Net-(SRC-SEL-Pad1)") (class "Default")
      (node (ref "SRC-SEL") (pin "1") (pinfunction "1_1") (pintype "passive"))
      (node (ref "X1") (pin "1") (pinfunction "1_1") (pintype "input"))
    )
    (net (code "63") (name "unconnected-(U$1-PadP$1)") (class "Default")
      (node (ref "U$1") (pin "P$1") (pinfunction "P$1_P$1") (pintype "bidirectional"))
    )
    (net (code "64") (name "unconnected-(U$1-PadP$2)") (class "Default")
      (node (ref "U$1") (pin "P$2") (pinfunction "P$2_P$2") (pintype "bidirectional"))
    )
    (net (code "65") (name "unconnected-(U$1-PadP$3)") (class "Default")
      (node (ref "U$1") (pin "P$3") (pinfunction "P$3_P$3") (pintype "bidirectional"))
    )
    (net (code "66") (name "unconnected-(U$1-PadP$4)") (class "Default")
      (node (ref "U$1") (pin "P$4") (pinfunction "P$4_P$4") (pintype "bidirectional"))
    )
    (net (code "67") (name "unconnected-(U$1-PadP$5)") (class "Default")
      (node (ref "U$1") (pin "P$5") (pinfunction "P$5_P$5") (pintype "bidirectional"))
    )
    (net (code "68") (name "unconnected-(U$1-PadP$6)") (class "Default")
      (node (ref "U$1") (pin "P$6") (pinfunction "P$6_P$6") (pintype "bidirectional"))
    )
    (net (code "69") (name "unconnected-(U$1-PadP$8)") (class "Default")
      (node (ref "U$1") (pin "P$8") (pinfunction "P$8_P$8") (pintype "bidirectional"))
    )
    (net (code "70") (name "unconnected-(U$1-PadP$32)") (class "Default")
      (node (ref "U$1") (pin "P$32") (pinfunction "P$32_P$32") (pintype "bidirectional"))
    )
    (net (code "71") (name "unconnected-(U$1-PadP$41)") (class "Default")
      (node (ref "U$1") (pin "P$41") (pinfunction "P$41_P$41") (pintype "bidirectional"))
    )
    (net (code "72") (name "unconnected-(U$1-PadP$43)") (class "Default")
      (node (ref "U$1") (pin "P$43") (pinfunction "P$43_P$43") (pintype "bidirectional"))
    )
    (net (code "73") (name "unconnected-(U$1-PadP$44)") (class "Default")
      (node (ref "U$1") (pin "P$44") (pinfunction "P$44_P$44") (pintype "bidirectional"))
    )
    (net (code "74") (name "unconnected-(U$1-PadP$45)") (class "Default")
      (node (ref "U$1") (pin "P$45") (pinfunction "P$45_P$45") (pintype "bidirectional"))
    )
    (net (code "75") (name "unconnected-(U$1-PadP$66)") (class "Default")
      (node (ref "U$1") (pin "P$66") (pinfunction "P$66_P$66") (pintype "bidirectional"))
    )
    (net (code "76") (name "unconnected-(U$1-PadP$75)") (class "Default")
      (node (ref "U$1") (pin "P$75") (pinfunction "P$75_P$75") (pintype "bidirectional"))
    )
    (net (code "77") (name "unconnected-(U$1-PadP$76)") (class "Default")
      (node (ref "U$1") (pin "P$76") (pinfunction "P$76_P$76") (pintype "bidirectional"))
    )
    (net (code "78") (name "unconnected-(U$1-PadP$77)") (class "Default")
      (node (ref "U$1") (pin "P$77") (pinfunction "P$77_P$77") (pintype "bidirectional"))
    )
    (net (code "79") (name "unconnected-(U$1-PadP$78)") (class "Default")
      (node (ref "U$1") (pin "P$78") (pinfunction "P$78_P$78") (pintype "bidirectional"))
    )
    (net (code "80") (name "unconnected-(U$1-PadP$79)") (class "Default")
      (node (ref "U$1") (pin "P$79") (pinfunction "P$79_P$79") (pintype "bidirectional"))
    )
    (net (code "81") (name "unconnected-(U$1-PadP$80)") (class "Default")
      (node (ref "U$1") (pin "P$80") (pinfunction "P$80_P$80") (pintype "bidirectional"))
    )
    (net (code "82") (name "unconnected-(U$1-PadP$81)") (class "Default")
      (node (ref "U$1") (pin "P$81") (pinfunction "P$81_P$81") (pintype "bidirectional"))
    )
    (net (code "83") (name "unconnected-(U$1-PadP$82)") (class "Default")
      (node (ref "U$1") (pin "P$82") (pinfunction "P$82_P$82") (pintype "bidirectional"))
    )
    (net (code "84") (name "unconnected-(U$1-PadP$85)") (class "Default")
      (node (ref "U$1") (pin "P$85") (pinfunction "P$85_P$85") (pintype "bidirectional"))
    )
    (net (code "85") (name "unconnected-(U$1-PadP$86)") (class "Default")
      (node (ref "U$1") (pin "P$86") (pinfunction "P$86_P$86") (pintype "bidirectional"))
    )
    (net (code "86") (name "unconnected-(U$1-PadP$87)") (class "Default")
      (node (ref "U$1") (pin "P$87") (pinfunction "P$87_P$87") (pintype "bidirectional"))
    )
    (net (code "87") (name "unconnected-(U$1-PadP$88)") (class "Default")
      (node (ref "U$1") (pin "P$88") (pinfunction "P$88_P$88") (pintype "bidirectional"))
    )
    (net (code "88") (name "unconnected-(U$1-PadP$89)") (class "Default")
      (node (ref "U$1") (pin "P$89") (pinfunction "P$89_P$89") (pintype "bidirectional"))
    )
    (net (code "89") (name "unconnected-(U$1-PadP$90)") (class "Default")
      (node (ref "U$1") (pin "P$90") (pinfunction "P$90_P$90") (pintype "bidirectional"))
    )
    (net (code "90") (name "unconnected-(U$1-PadP$91)") (class "Default")
      (node (ref "U$1") (pin "P$91") (pinfunction "P$91_P$91") (pintype "bidirectional"))
    )
    (net (code "91") (name "unconnected-(U$1-PadP$92)") (class "Default")
      (node (ref "U$1") (pin "P$92") (pinfunction "P$92_P$92") (pintype "bidirectional"))
    )
    (net (code "92") (name "unconnected-(U$1-PadP$93)") (class "Default")
      (node (ref "U$1") (pin "P$93") (pinfunction "P$93_P$93") (pintype "bidirectional"))
    )
    (net (code "93") (name "unconnected-(U$1-PadP$94)") (class "Default")
      (node (ref "U$1") (pin "P$94") (pinfunction "P$94_P$94") (pintype "bidirectional"))
    )
    (net (code "94") (name "unconnected-(U$1-PadP$95)") (class "Default")
      (node (ref "U$1") (pin "P$95") (pinfunction "P$95_P$95") (pintype "bidirectional"))
    )
    (net (code "95") (name "unconnected-(U$1-PadP$96)") (class "Default")
      (node (ref "U$1") (pin "P$96") (pinfunction "P$96_P$96") (pintype "bidirectional"))
    )
    (net (code "96") (name "unconnected-(U$1-PadP$99)") (class "Default")
      (node (ref "U$1") (pin "P$99") (pinfunction "P$99_P$99") (pintype "bidirectional"))
    )
    (net (code "97") (name "unconnected-(U$1-PadP$101)") (class "Default")
      (node (ref "U$1") (pin "P$101") (pinfunction "P$101_P$101") (pintype "bidirectional"))
    )
    (net (code "98") (name "unconnected-(U$1-PadP$103)") (class "Default")
      (node (ref "U$1") (pin "P$103") (pinfunction "P$103_P$103") (pintype "bidirectional"))
    )
    (net (code "99") (name "unconnected-(U$1-PadP$105)") (class "Default")
      (node (ref "U$1") (pin "P$105") (pinfunction "P$105_P$105") (pintype "bidirectional"))
    )
    (net (code "100") (name "unconnected-(U$1-PadP$107)") (class "Default")
      (node (ref "U$1") (pin "P$107") (pinfunction "P$107_P$107") (pintype "bidirectional"))
    )
    (net (code "101") (name "unconnected-(U$1-PadP$109)") (class "Default")
      (node (ref "U$1") (pin "P$109") (pinfunction "P$109_P$109") (pintype "bidirectional"))
    )
    (net (code "102") (name "unconnected-(U$1-PadP$113)") (class "Default")
      (node (ref "U$1") (pin "P$113") (pinfunction "P$113_P$113") (pintype "bidirectional"))
    )
    (net (code "103") (name "unconnected-(U$1-PadP$114)") (class "Default")
      (node (ref "U$1") (pin "P$114") (pinfunction "P$114_P$114") (pintype "bidirectional"))
    )
    (net (code "104") (name "unconnected-(U$1-PadP$115)") (class "Default")
      (node (ref "U$1") (pin "P$115") (pinfunction "P$115_P$115") (pintype "bidirectional"))
    )
    (net (code "105") (name "unconnected-(U$1-PadP$116)") (class "Default")
      (node (ref "U$1") (pin "P$116") (pinfunction "P$116_P$116") (pintype "bidirectional"))
    )
    (net (code "106") (name "unconnected-(U$1-PadP$117)") (class "Default")
      (node (ref "U$1") (pin "P$117") (pinfunction "P$117_P$117") (pintype "bidirectional"))
    )
    (net (code "107") (name "unconnected-(U$1-PadP$118)") (class "Default")
      (node (ref "U$1") (pin "P$118") (pinfunction "P$118_P$118") (pintype "bidirectional"))
    )
    (net (code "108") (name "unconnected-(U$1-PadP$119)") (class "Default")
      (node (ref "U$1") (pin "P$119") (pinfunction "P$119_P$119") (pintype "bidirectional"))
    )
    (net (code "109") (name "unconnected-(U$1-PadP$120)") (class "Default")
      (node (ref "U$1") (pin "P$120") (pinfunction "P$120_P$120") (pintype "bidirectional"))
    )
    (net (code "110") (name "unconnected-(U$2-P$121-PadP$1)") (class "Default")
      (node (ref "U$2") (pin "P$1") (pinfunction "P$121_P$1") (pintype "bidirectional"))
    )
    (net (code "111") (name "unconnected-(U$2-P$122-PadP$2)") (class "Default")
      (node (ref "U$2") (pin "P$2") (pinfunction "P$122_P$2") (pintype "bidirectional"))
    )
    (net (code "112") (name "unconnected-(U$2-P$123-PadP$3)") (class "Default")
      (node (ref "U$2") (pin "P$3") (pinfunction "P$123_P$3") (pintype "bidirectional"))
    )
    (net (code "113") (name "unconnected-(U$2-P$124-PadP$4)") (class "Default")
      (node (ref "U$2") (pin "P$4") (pinfunction "P$124_P$4") (pintype "bidirectional"))
    )
    (net (code "114") (name "unconnected-(U$2-P$125-PadP$5)") (class "Default")
      (node (ref "U$2") (pin "P$5") (pinfunction "P$125_P$5") (pintype "bidirectional"))
    )
    (net (code "115") (name "unconnected-(U$2-P$126-PadP$6)") (class "Default")
      (node (ref "U$2") (pin "P$6") (pinfunction "P$126_P$6") (pintype "bidirectional"))
    )
    (net (code "116") (name "unconnected-(U$2-P$127-PadP$7)") (class "Default")
      (node (ref "U$2") (pin "P$7") (pinfunction "P$127_P$7") (pintype "bidirectional"))
    )
    (net (code "117") (name "unconnected-(U$2-P$128-PadP$8)") (class "Default")
      (node (ref "U$2") (pin "P$8") (pinfunction "P$128_P$8") (pintype "bidirectional"))
    )
    (net (code "118") (name "unconnected-(U$2-P$129-PadP$9)") (class "Default")
      (node (ref "U$2") (pin "P$9") (pinfunction "P$129_P$9") (pintype "bidirectional"))
    )
    (net (code "119") (name "unconnected-(U$2-P$130-PadP$10)") (class "Default")
      (node (ref "U$2") (pin "P$10") (pinfunction "P$130_P$10") (pintype "bidirectional"))
    )
    (net (code "120") (name "unconnected-(U$2-P$131-PadP$11)") (class "Default")
      (node (ref "U$2") (pin "P$11") (pinfunction "P$131_P$11") (pintype "bidirectional"))
    )
    (net (code "121") (name "unconnected-(U$2-P$132-PadP$12)") (class "Default")
      (node (ref "U$2") (pin "P$12") (pinfunction "P$132_P$12") (pintype "bidirectional"))
    )
    (net (code "122") (name "unconnected-(U$2-P$133-PadP$13)") (class "Default")
      (node (ref "U$2") (pin "P$13") (pinfunction "P$133_P$13") (pintype "bidirectional"))
    )
    (net (code "123") (name "unconnected-(U$2-P$134-PadP$14)") (class "Default")
      (node (ref "U$2") (pin "P$14") (pinfunction "P$134_P$14") (pintype "bidirectional"))
    )
    (net (code "124") (name "unconnected-(U$2-P$136-PadP$16)") (class "Default")
      (node (ref "U$2") (pin "P$16") (pinfunction "P$136_P$16") (pintype "bidirectional"))
    )
    (net (code "125") (name "unconnected-(U$2-P$137-PadP$17)") (class "Default")
      (node (ref "U$2") (pin "P$17") (pinfunction "P$137_P$17") (pintype "bidirectional"))
    )
    (net (code "126") (name "unconnected-(U$2-P$138-PadP$18)") (class "Default")
      (node (ref "U$2") (pin "P$18") (pinfunction "P$138_P$18") (pintype "bidirectional"))
    )
    (net (code "127") (name "unconnected-(U$2-P$139-PadP$19)") (class "Default")
      (node (ref "U$2") (pin "P$19") (pinfunction "P$139_P$19") (pintype "bidirectional"))
    )
    (net (code "128") (name "unconnected-(U$2-P$140-PadP$20)") (class "Default")
      (node (ref "U$2") (pin "P$20") (pinfunction "P$140_P$20") (pintype "bidirectional"))
    )
    (net (code "129") (name "unconnected-(U$2-P$141-PadP$21)") (class "Default")
      (node (ref "U$2") (pin "P$21") (pinfunction "P$141_P$21") (pintype "bidirectional"))
    )
    (net (code "130") (name "unconnected-(U$2-P$142-PadP$22)") (class "Default")
      (node (ref "U$2") (pin "P$22") (pinfunction "P$142_P$22") (pintype "bidirectional"))
    )
    (net (code "131") (name "unconnected-(U$2-P$143-PadP$23)") (class "Default")
      (node (ref "U$2") (pin "P$23") (pinfunction "P$143_P$23") (pintype "bidirectional"))
    )
    (net (code "132") (name "unconnected-(U$2-P$144-PadP$24)") (class "Default")
      (node (ref "U$2") (pin "P$24") (pinfunction "P$144_P$24") (pintype "bidirectional"))
    )
    (net (code "133") (name "unconnected-(U$2-P$145-PadP$25)") (class "Default")
      (node (ref "U$2") (pin "P$25") (pinfunction "P$145_P$25") (pintype "bidirectional"))
    )
    (net (code "134") (name "unconnected-(U$2-P$146-PadP$26)") (class "Default")
      (node (ref "U$2") (pin "P$26") (pinfunction "P$146_P$26") (pintype "bidirectional"))
    )
    (net (code "135") (name "unconnected-(U$2-P$147-PadP$27)") (class "Default")
      (node (ref "U$2") (pin "P$27") (pinfunction "P$147_P$27") (pintype "bidirectional"))
    )
    (net (code "136") (name "unconnected-(U$2-P$148-PadP$28)") (class "Default")
      (node (ref "U$2") (pin "P$28") (pinfunction "P$148_P$28") (pintype "bidirectional"))
    )
    (net (code "137") (name "unconnected-(U$2-P$149-PadP$29)") (class "Default")
      (node (ref "U$2") (pin "P$29") (pinfunction "P$149_P$29") (pintype "bidirectional"))
    )
    (net (code "138") (name "unconnected-(U$2-P$150-PadP$30)") (class "Default")
      (node (ref "U$2") (pin "P$30") (pinfunction "P$150_P$30") (pintype "bidirectional"))
    )
    (net (code "139") (name "unconnected-(U$2-P$151-PadP$31)") (class "Default")
      (node (ref "U$2") (pin "P$31") (pinfunction "P$151_P$31") (pintype "bidirectional"))
    )
    (net (code "140") (name "unconnected-(U$2-P$152-PadP$32)") (class "Default")
      (node (ref "U$2") (pin "P$32") (pinfunction "P$152_P$32") (pintype "bidirectional"))
    )
    (net (code "141") (name "unconnected-(U$2-P$153-PadP$33)") (class "Default")
      (node (ref "U$2") (pin "P$33") (pinfunction "P$153_P$33") (pintype "bidirectional"))
    )
    (net (code "142") (name "unconnected-(U$2-P$154-PadP$34)") (class "Default")
      (node (ref "U$2") (pin "P$34") (pinfunction "P$154_P$34") (pintype "bidirectional"))
    )
    (net (code "143") (name "unconnected-(U$2-P$155-PadP$35)") (class "Default")
      (node (ref "U$2") (pin "P$35") (pinfunction "P$155_P$35") (pintype "bidirectional"))
    )
    (net (code "144") (name "unconnected-(U$2-P$156-PadP$36)") (class "Default")
      (node (ref "U$2") (pin "P$36") (pinfunction "P$156_P$36") (pintype "bidirectional"))
    )
    (net (code "145") (name "unconnected-(U$2-P$159-PadP$39)") (class "Default")
      (node (ref "U$2") (pin "P$39") (pinfunction "P$159_P$39") (pintype "bidirectional"))
    )
    (net (code "146") (name "unconnected-(U$2-P$160-PadP$40)") (class "Default")
      (node (ref "U$2") (pin "P$40") (pinfunction "P$160_P$40") (pintype "bidirectional"))
    )
    (net (code "147") (name "unconnected-(U$2-P$161-PadP$41)") (class "Default")
      (node (ref "U$2") (pin "P$41") (pinfunction "P$161_P$41") (pintype "bidirectional"))
    )
    (net (code "148") (name "unconnected-(U$2-P$162-PadP$42)") (class "Default")
      (node (ref "U$2") (pin "P$42") (pinfunction "P$162_P$42") (pintype "bidirectional"))
    )
    (net (code "149") (name "unconnected-(U$2-P$163-PadP$43)") (class "Default")
      (node (ref "U$2") (pin "P$43") (pinfunction "P$163_P$43") (pintype "bidirectional"))
    )
    (net (code "150") (name "unconnected-(U$2-P$164-PadP$44)") (class "Default")
      (node (ref "U$2") (pin "P$44") (pinfunction "P$164_P$44") (pintype "bidirectional"))
    )
    (net (code "151") (name "unconnected-(U$2-P$165-PadP$45)") (class "Default")
      (node (ref "U$2") (pin "P$45") (pinfunction "P$165_P$45") (pintype "bidirectional"))
    )
    (net (code "152") (name "unconnected-(U$2-P$166-PadP$46)") (class "Default")
      (node (ref "U$2") (pin "P$46") (pinfunction "P$166_P$46") (pintype "bidirectional"))
    )
    (net (code "153") (name "unconnected-(U$2-P$167-PadP$47)") (class "Default")
      (node (ref "U$2") (pin "P$47") (pinfunction "P$167_P$47") (pintype "bidirectional"))
    )
    (net (code "154") (name "unconnected-(U$2-P$168-PadP$48)") (class "Default")
      (node (ref "U$2") (pin "P$48") (pinfunction "P$168_P$48") (pintype "bidirectional"))
    )
    (net (code "155") (name "unconnected-(U$2-P$169-PadP$49)") (class "Default")
      (node (ref "U$2") (pin "P$49") (pinfunction "P$169_P$49") (pintype "bidirectional"))
    )
    (net (code "156") (name "unconnected-(U$2-P$170-PadP$50)") (class "Default")
      (node (ref "U$2") (pin "P$50") (pinfunction "P$170_P$50") (pintype "bidirectional"))
    )
    (net (code "157") (name "unconnected-(U$2-P$171-PadP$51)") (class "Default")
      (node (ref "U$2") (pin "P$51") (pinfunction "P$171_P$51") (pintype "bidirectional"))
    )
    (net (code "158") (name "unconnected-(U$2-P$172-PadP$52)") (class "Default")
      (node (ref "U$2") (pin "P$52") (pinfunction "P$172_P$52") (pintype "bidirectional"))
    )
    (net (code "159") (name "unconnected-(U$2-P$173-PadP$53)") (class "Default")
      (node (ref "U$2") (pin "P$53") (pinfunction "P$173_P$53") (pintype "bidirectional"))
    )
    (net (code "160") (name "unconnected-(U$2-P$174-PadP$54)") (class "Default")
      (node (ref "U$2") (pin "P$54") (pinfunction "P$174_P$54") (pintype "bidirectional"))
    )
    (net (code "161") (name "unconnected-(U$2-P$175-PadP$55)") (class "Default")
      (node (ref "U$2") (pin "P$55") (pinfunction "P$175_P$55") (pintype "bidirectional"))
    )
    (net (code "162") (name "unconnected-(U$2-P$176-PadP$56)") (class "Default")
      (node (ref "U$2") (pin "P$56") (pinfunction "P$176_P$56") (pintype "bidirectional"))
    )
    (net (code "163") (name "unconnected-(U$2-P$177-PadP$57)") (class "Default")
      (node (ref "U$2") (pin "P$57") (pinfunction "P$177_P$57") (pintype "bidirectional"))
    )
    (net (code "164") (name "unconnected-(U$2-P$178-PadP$58)") (class "Default")
      (node (ref "U$2") (pin "P$58") (pinfunction "P$178_P$58") (pintype "bidirectional"))
    )
    (net (code "165") (name "unconnected-(X1-Pad2)") (class "Default")
      (node (ref "X1") (pin "2") (pinfunction "2_2") (pintype "input"))
    )
    (net (code "166") (name "unconnected-(X1-Pad3)") (class "Default")
      (node (ref "X1") (pin "3") (pinfunction "3_3") (pintype "input"))
    )
    (net (code "167") (name "unconnected-(X1-Pad4)") (class "Default")
      (node (ref "X1") (pin "4") (pinfunction "4_4") (pintype "input"))
    )
    (net (code "168") (name "~{LF_LEG_0}") (class "Default")
      (node (ref "LF_INV") (pin "2") (pinfunction "1Y_2") (pintype "output"))
      (node (ref "SV21") (pin "1") (pinfunction "1_1") (pintype "passive"))
    )
    (net (code "169") (name "~{LF_LEG_1}") (class "Default")
      (node (ref "LF_INV") (pin "4") (pinfunction "2Y_4") (pintype "output"))
      (node (ref "SV21") (pin "2") (pinfunction "2_2") (pintype "passive"))
    )
    (net (code "170") (name "~{LF_LEG_2}") (class "Default")
      (node (ref "LF_INV") (pin "6") (pinfunction "3Y_6") (pintype "output"))
      (node (ref "SV21") (pin "3") (pinfunction "3_3") (pintype "passive"))
    )
    (net (code "171") (name "~{LF_LEG_3}") (class "Default")
      (node (ref "LF_INV") (pin "8") (pinfunction "4Y_8") (pintype "output"))
      (node (ref "SV21") (pin "4") (pinfunction "4_4") (pintype "passive"))
    )
    (net (code "172") (name "~{LF_LEG_4}") (class "Default")
      (node (ref "LF_INV") (pin "10") (pinfunction "5Y_10") (pintype "output"))
      (node (ref "SV21") (pin "5") (pinfunction "5_5") (pintype "passive"))
    )
    (net (code "173") (name "~{LF_LEG_5}") (class "Default")
      (node (ref "LF_INV") (pin "12") (pinfunction "6Y_12") (pintype "output"))
      (node (ref "SV21") (pin "6") (pinfunction "6_6") (pintype "passive"))
    )
    (net (code "174") (name "~{LF_PHASE_U}") (class "Default")
      (node (ref "SV23") (pin "2") (pinfunction "2_2") (pintype "passive"))
      (node (ref "SV7") (pin "1") (pinfunction "1_1") (pintype "passive"))
      (node (ref "SV7") (pin "10") (pinfunction "10_10") (pintype "passive"))
      (node (ref "SV7") (pin "11") (pinfunction "11_11") (pintype "passive"))
      (node (ref "SV7") (pin "12") (pinfunction "12_12") (pintype "passive"))
      (node (ref "SV7") (pin "2") (pinfunction "2_2") (pintype "passive"))
      (node (ref "SV7") (pin "3") (pinfunction "3_3") (pintype "passive"))
      (node (ref "SV7") (pin "4") (pinfunction "4_4") (pintype "passive"))
      (node (ref "SV7") (pin "5") (pinfunction "5_5") (pintype "passive"))
      (node (ref "SV7") (pin "6") (pinfunction "6_6") (pintype "passive"))
      (node (ref "SV7") (pin "7") (pinfunction "7_7") (pintype "passive"))
      (node (ref "SV7") (pin "8") (pinfunction "8_8") (pintype "passive"))
      (node (ref "SV7") (pin "9") (pinfunction "9_9") (pintype "passive"))
      (node (ref "SV8") (pin "1") (pinfunction "1_1") (pintype "passive"))
      (node (ref "SV8") (pin "10") (pinfunction "10_10") (pintype "passive"))
      (node (ref "SV8") (pin "11") (pinfunction "11_11") (pintype "passive"))
      (node (ref "SV8") (pin "12") (pinfunction "12_12") (pintype "passive"))
      (node (ref "SV8") (pin "2") (pinfunction "2_2") (pintype "passive"))
      (node (ref "SV8") (pin "3") (pinfunction "3_3") (pintype "passive"))
      (node (ref "SV8") (pin "4") (pinfunction "4_4") (pintype "passive"))
      (node (ref "SV8") (pin "5") (pinfunction "5_5") (pintype "passive"))
      (node (ref "SV8") (pin "6") (pinfunction "6_6") (pintype "passive"))
      (node (ref "SV8") (pin "7") (pinfunction "7_7") (pintype "passive"))
      (node (ref "SV8") (pin "8") (pinfunction "8_8") (pintype "passive"))
      (node (ref "SV8") (pin "9") (pinfunction "9_9") (pintype "passive"))
    )
    (net (code "175") (name "~{LF_PHASE_V}") (class "Default")
      (node (ref "SV15") (pin "1") (pinfunction "1_1") (pintype "passive"))
      (node (ref "SV15") (pin "10") (pinfunction "10_10") (pintype "passive"))
      (node (ref "SV15") (pin "11") (pinfunction "11_11") (pintype "passive"))
      (node (ref "SV15") (pin "12") (pinfunction "12_12") (pintype "passive"))
      (node (ref "SV15") (pin "2") (pinfunction "2_2") (pintype "passive"))
      (node (ref "SV15") (pin "3") (pinfunction "3_3") (pintype "passive"))
      (node (ref "SV15") (pin "4") (pinfunction "4_4") (pintype "passive"))
      (node (ref "SV15") (pin "5") (pinfunction "5_5") (pintype "passive"))
      (node (ref "SV15") (pin "6") (pinfunction "6_6") (pintype "passive"))
      (node (ref "SV15") (pin "7") (pinfunction "7_7") (pintype "passive"))
      (node (ref "SV15") (pin "8") (pinfunction "8_8") (pintype "passive"))
      (node (ref "SV15") (pin "9") (pinfunction "9_9") (pintype "passive"))
      (node (ref "SV16") (pin "1") (pinfunction "1_1") (pintype "passive"))
      (node (ref "SV16") (pin "10") (pinfunction "10_10") (pintype "passive"))
      (node (ref "SV16") (pin "11") (pinfunction "11_11") (pintype "passive"))
      (node (ref "SV16") (pin "12") (pinfunction "12_12") (pintype "passive"))
      (node (ref "SV16") (pin "2") (pinfunction "2_2") (pintype "passive"))
      (node (ref "SV16") (pin "3") (pinfunction "3_3") (pintype "passive"))
      (node (ref "SV16") (pin "4") (pinfunction "4_4") (pintype "passive"))
      (node (ref "SV16") (pin "5") (pinfunction "5_5") (pintype "passive"))
      (node (ref "SV16") (pin "6") (pinfunction "6_6") (pintype "passive"))
      (node (ref "SV16") (pin "7") (pinfunction "7_7") (pintype "passive"))
      (node (ref "SV16") (pin "8") (pinfunction "8_8") (pintype "passive"))
      (node (ref "SV16") (pin "9") (pinfunction "9_9") (pintype "passive"))
      (node (ref "SV23") (pin "4") (pinfunction "4_4") (pintype "passive"))
    )
    (net (code "176") (name "~{LF_PHASE_W}") (class "Default")
      (node (ref "SV19") (pin "1") (pinfunction "1_1") (pintype "passive"))
      (node (ref "SV19") (pin "10") (pinfunction "10_10") (pintype "passive"))
      (node (ref "SV19") (pin "11") (pinfunction "11_11") (pintype "passive"))
      (node (ref "SV19") (pin "12") (pinfunction "12_12") (pintype "passive"))
      (node (ref "SV19") (pin "2") (pinfunction "2_2") (pintype "passive"))
      (node (ref "SV19") (pin "3") (pinfunction "3_3") (pintype "passive"))
      (node (ref "SV19") (pin "4") (pinfunction "4_4") (pintype "passive"))
      (node (ref "SV19") (pin "5") (pinfunction "5_5") (pintype "passive"))
      (node (ref "SV19") (pin "6") (pinfunction "6_6") (pintype "passive"))
      (node (ref "SV19") (pin "7") (pinfunction "7_7") (pintype "passive"))
      (node (ref "SV19") (pin "8") (pinfunction "8_8") (pintype "passive"))
      (node (ref "SV19") (pin "9") (pinfunction "9_9") (pintype "passive"))
      (node (ref "SV20") (pin "1") (pinfunction "1_1") (pintype "passive"))
      (node (ref "SV20") (pin "10") (pinfunction "10_10") (pintype "passive"))
      (node (ref "SV20") (pin "11") (pinfunction "11_11") (pintype "passive"))
      (node (ref "SV20") (pin "12") (pinfunction "12_12") (pintype "passive"))
      (node (ref "SV20") (pin "2") (pinfunction "2_2") (pintype "passive"))
      (node (ref "SV20") (pin "3") (pinfunction "3_3") (pintype "passive"))
      (node (ref "SV20") (pin "4") (pinfunction "4_4") (pintype "passive"))
      (node (ref "SV20") (pin "5") (pinfunction "5_5") (pintype "passive"))
      (node (ref "SV20") (pin "6") (pinfunction "6_6") (pintype "passive"))
      (node (ref "SV20") (pin "7") (pinfunction "7_7") (pintype "passive"))
      (node (ref "SV20") (pin "8") (pinfunction "8_8") (pintype "passive"))
      (node (ref "SV20") (pin "9") (pinfunction "9_9") (pintype "passive"))
      (node (ref "SV23") (pin "6") (pinfunction "6_6") (pintype "passive"))
    )
    (net (code "177") (name "~{PWM00}") (class "Default")
      (node (ref "HEXINV_1") (pin "2") (pinfunction "1Y_2") (pintype "output"))
      (node (ref "SV3") (pin "1") (pinfunction "1_1") (pintype "passive"))
    )
    (net (code "178") (name "~{PWM01}") (class "Default")
      (node (ref "HEXINV_1") (pin "4") (pinfunction "2Y_4") (pintype "output"))
      (node (ref "SV3") (pin "2") (pinfunction "2_2") (pintype "passive"))
    )
    (net (code "179") (name "~{PWM02}") (class "Default")
      (node (ref "HEXINV_1") (pin "6") (pinfunction "3Y_6") (pintype "output"))
      (node (ref "SV3") (pin "3") (pinfunction "3_3") (pintype "passive"))
    )
    (net (code "180") (name "~{PWM03}") (class "Default")
      (node (ref "HEXINV_1") (pin "8") (pinfunction "4Y_8") (pintype "output"))
      (node (ref "SV3") (pin "4") (pinfunction "4_4") (pintype "passive"))
    )
    (net (code "181") (name "~{PWM04}") (class "Default")
      (node (ref "HEXINV_1") (pin "10") (pinfunction "5Y_10") (pintype "output"))
      (node (ref "SV3") (pin "5") (pinfunction "5_5") (pintype "passive"))
    )
    (net (code "182") (name "~{PWM05}") (class "Default")
      (node (ref "HEXINV_1") (pin "12") (pinfunction "6Y_12") (pintype "output"))
      (node (ref "SV3") (pin "6") (pinfunction "6_6") (pintype "passive"))
    )
    (net (code "183") (name "~{PWM06}") (class "Default")
      (node (ref "HEXINV_2") (pin "2") (pinfunction "1Y_2") (pintype "output"))
      (node (ref "SV3") (pin "7") (pinfunction "7_7") (pintype "passive"))
    )
    (net (code "184") (name "~{PWM07}") (class "Default")
      (node (ref "HEXINV_2") (pin "4") (pinfunction "2Y_4") (pintype "output"))
      (node (ref "SV3") (pin "8") (pinfunction "8_8") (pintype "passive"))
    )
    (net (code "185") (name "~{PWM08}") (class "Default")
      (node (ref "HEXINV_2") (pin "6") (pinfunction "3Y_6") (pintype "output"))
      (node (ref "SV3") (pin "9") (pinfunction "9_9") (pintype "passive"))
    )
    (net (code "186") (name "~{PWM09}") (class "Default")
      (node (ref "HEXINV_2") (pin "8") (pinfunction "4Y_8") (pintype "output"))
      (node (ref "SV3") (pin "10") (pinfunction "10_10") (pintype "passive"))
    )
    (net (code "187") (name "~{PWM10}") (class "Default")
      (node (ref "HEXINV_2") (pin "10") (pinfunction "5Y_10") (pintype "output"))
      (node (ref "SV3") (pin "11") (pinfunction "11_11") (pintype "passive"))
    )
    (net (code "188") (name "~{PWM11}") (class "Default")
      (node (ref "HEXINV_2") (pin "12") (pinfunction "6Y_12") (pintype "output"))
      (node (ref "SV3") (pin "12") (pinfunction "12_12") (pintype "passive"))
    )
    (net (code "189") (name "~{PWM12}") (class "Default")
      (node (ref "HEXINV_3") (pin "2") (pinfunction "1Y_2") (pintype "output"))
      (node (ref "SV4") (pin "1") (pinfunction "1_1") (pintype "passive"))
    )
    (net (code "190") (name "~{PWM13}") (class "Default")
      (node (ref "HEXINV_3") (pin "4") (pinfunction "2Y_4") (pintype "output"))
      (node (ref "SV4") (pin "2") (pinfunction "2_2") (pintype "passive"))
    )
    (net (code "191") (name "~{PWM14}") (class "Default")
      (node (ref "HEXINV_3") (pin "6") (pinfunction "3Y_6") (pintype "output"))
      (node (ref "SV4") (pin "3") (pinfunction "3_3") (pintype "passive"))
    )
    (net (code "192") (name "~{PWM15}") (class "Default")
      (node (ref "HEXINV_3") (pin "8") (pinfunction "4Y_8") (pintype "output"))
      (node (ref "SV4") (pin "4") (pinfunction "4_4") (pintype "passive"))
    )
    (net (code "193") (name "~{PWM16}") (class "Default")
      (node (ref "HEXINV_3") (pin "10") (pinfunction "5Y_10") (pintype "output"))
      (node (ref "SV4") (pin "5") (pinfunction "5_5") (pintype "passive"))
    )
    (net (code "194") (name "~{PWM17}") (class "Default")
      (node (ref "HEXINV_3") (pin "12") (pinfunction "6Y_12") (pintype "output"))
      (node (ref "SV4") (pin "6") (pinfunction "6_6") (pintype "passive"))
    )
    (net (code "195") (name "~{PWM18}") (class "Default")
      (node (ref "HEXINV_4") (pin "2") (pinfunction "1Y_2") (pintype "output"))
      (node (ref "SV4") (pin "7") (pinfunction "7_7") (pintype "passive"))
    )
    (net (code "196") (name "~{PWM19}") (class "Default")
      (node (ref "HEXINV_4") (pin "4") (pinfunction "2Y_4") (pintype "output"))
      (node (ref "SV4") (pin "8") (pinfunction "8_8") (pintype "passive"))
    )
    (net (code "197") (name "~{PWM20}") (class "Default")
      (node (ref "HEXINV_4") (pin "6") (pinfunction "3Y_6") (pintype "output"))
      (node (ref "SV4") (pin "9") (pinfunction "9_9") (pintype "passive"))
    )
    (net (code "198") (name "~{PWM21}") (class "Default")
      (node (ref "HEXINV_4") (pin "8") (pinfunction "4Y_8") (pintype "output"))
      (node (ref "SV4") (pin "10") (pinfunction "10_10") (pintype "passive"))
    )
    (net (code "199") (name "~{PWM22}") (class "Default")
      (node (ref "HEXINV_4") (pin "10") (pinfunction "5Y_10") (pintype "output"))
      (node (ref "SV4") (pin "11") (pinfunction "11_11") (pintype "passive"))
    )
    (net (code "200") (name "~{PWM23}") (class "Default")
      (node (ref "HEXINV_4") (pin "12") (pinfunction "6Y_12") (pintype "output"))
      (node (ref "SV4") (pin "12") (pinfunction "12_12") (pintype "passive"))
    )
  )
)
